# Salico_Controller_Module.net
KiCad netlist of a schematic drawn in Altium Designer
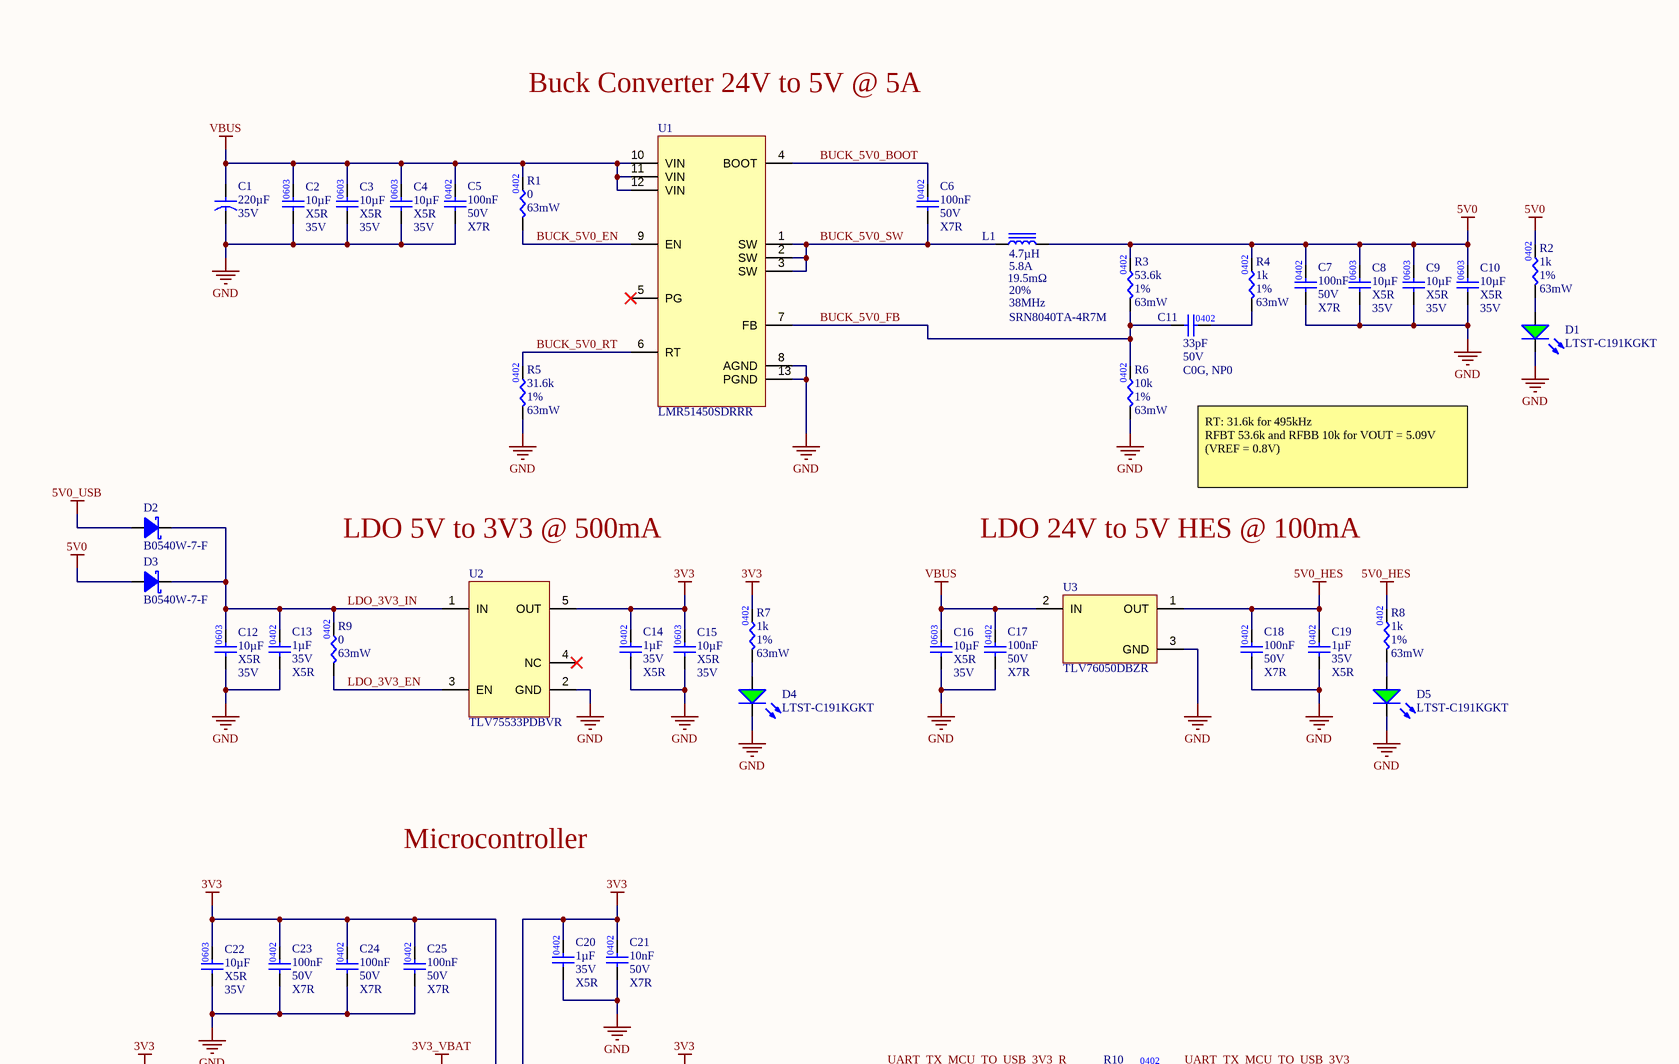
[diagram p0: Salico Controller Module.SchDoc, top left]
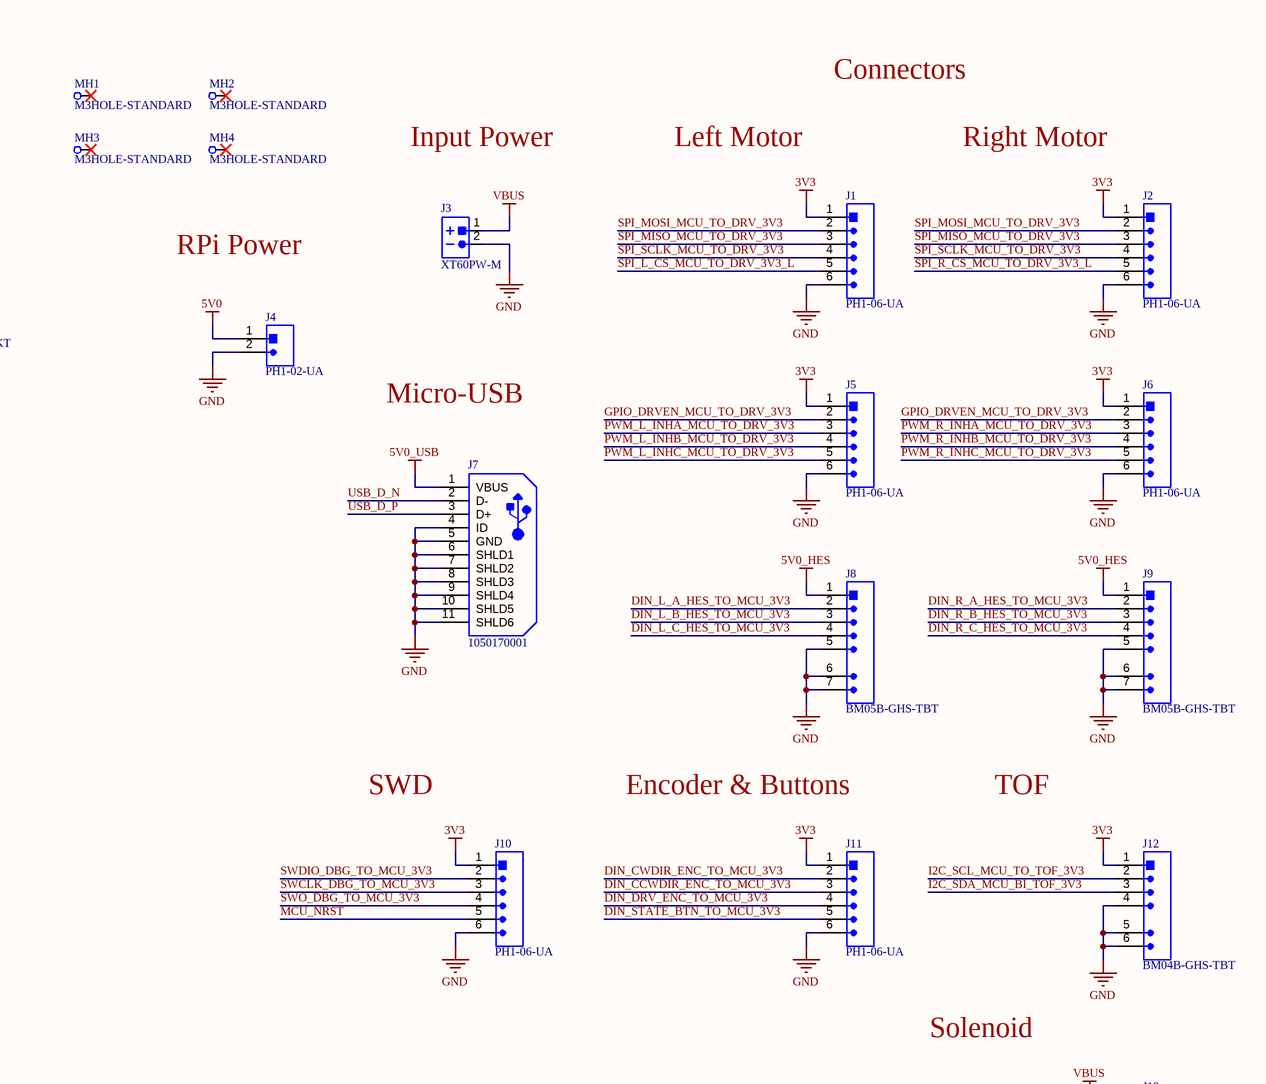
[diagram p1: Salico Controller Module.SchDoc, top right]
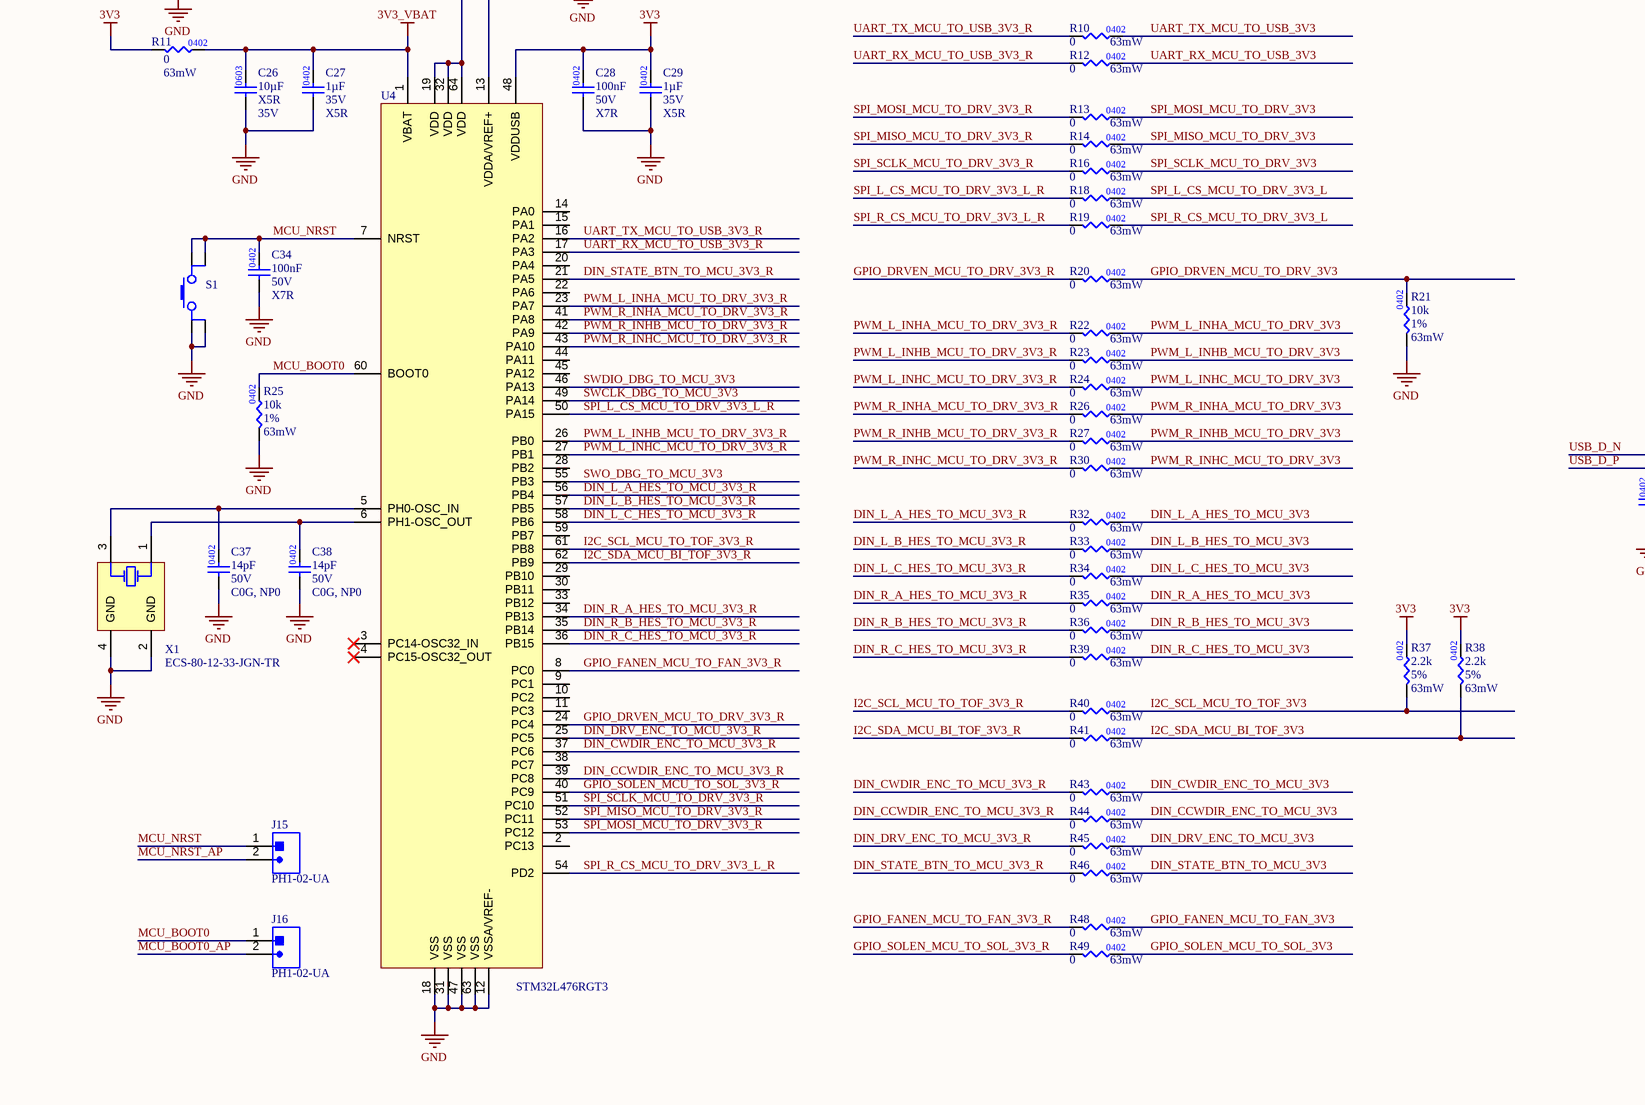
[diagram p2: Salico Controller Module.SchDoc, bottom left]
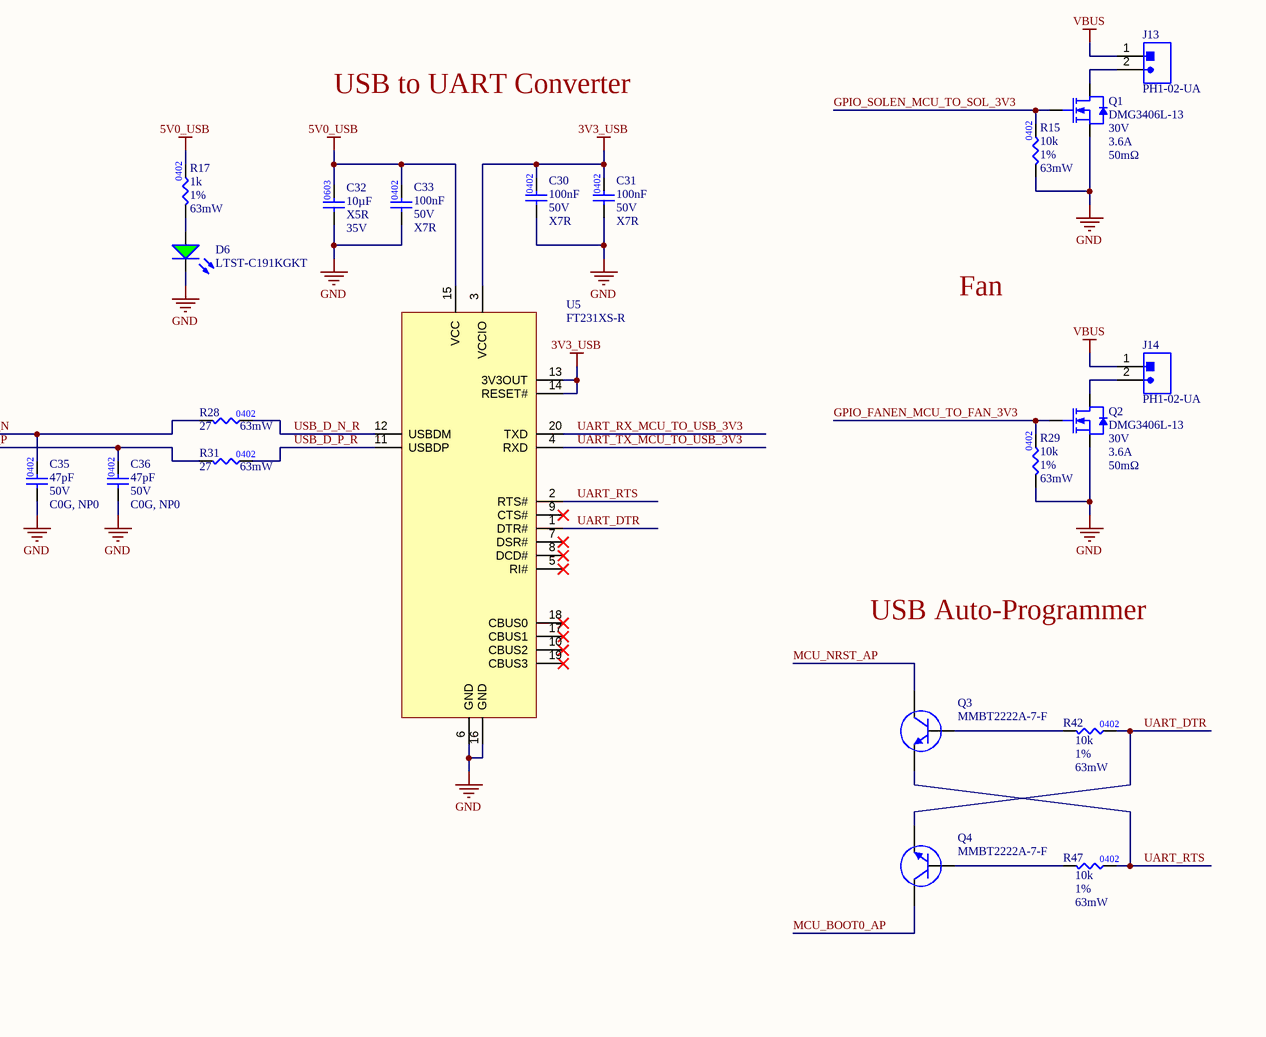
[diagram p3: Salico Controller Module.SchDoc, bottom right]

(export (version "E")
  (design (tool "Eeschema 10.0.6"))
  (components
    (comp (ref "C1")
      (value "220µF")
      (footprint "865080553014-Footprint-1")
      (description "CAP ALUM 220UF 20% 35V SMD")
      (fields
        (field (name "TOLERANCE") "20%")
        (field (name "VOLTAGE RATING") "35V")
        (field (name "Comment") "865080553014")
      )
      (libsource (lib "Americas - University of Waterloo - Kevin Li Capstone 2025") (part "865080553014-Symbol-1"))
    )
    (comp (ref "C2")
      (value "10µF")
      (footprint ".CAP_0603-Footprint-1")
      (description "CAP CER 10UF 35V X5R 0603")
      (fields
        (field (name "TEMPERATURE COEFFICIENT") "X5R")
        (field (name "VOLTAGE RATING") "35V")
        (field (name "TOLERANCE") "20%")
        (field (name "Comment") "GRM188R6YA106MA73D")
      )
      (libsource (lib "Americas - University of Waterloo - Kevin Li Capstone 2025") (part ".CAP_0603-Symbol-1"))
    )
    (comp (ref "C3")
      (value "10µF")
      (footprint ".CAP_0603-Footprint-1")
      (description "CAP CER 10UF 35V X5R 0603")
      (fields
        (field (name "TEMPERATURE COEFFICIENT") "X5R")
        (field (name "VOLTAGE RATING") "35V")
        (field (name "TOLERANCE") "20%")
        (field (name "Comment") "GRM188R6YA106MA73D")
      )
      (libsource (lib "Americas - University of Waterloo - Kevin Li Capstone 2025") (part ".CAP_0603-Symbol-1"))
    )
    (comp (ref "C4")
      (value "10µF")
      (footprint ".CAP_0603-Footprint-1")
      (description "CAP CER 10UF 35V X5R 0603")
      (fields
        (field (name "TEMPERATURE COEFFICIENT") "X5R")
        (field (name "VOLTAGE RATING") "35V")
        (field (name "TOLERANCE") "20%")
        (field (name "Comment") "GRM188R6YA106MA73D")
      )
      (libsource (lib "Americas - University of Waterloo - Kevin Li Capstone 2025") (part ".CAP_0603-Symbol-1"))
    )
    (comp (ref "C5")
      (value "100nF")
      (footprint ".CAP_0402-Footprint-1")
      (description "CAP CER 0.1UF 50V X7R 0402")
      (fields
        (field (name "VOLTAGE RATING") "50V")
        (field (name "TEMPERATURE COEFFICIENT") "X7R")
        (field (name "TOLERANCE") "10%")
        (field (name "Comment") "GCM155R71H104KE02D")
      )
      (libsource (lib "Americas - University of Waterloo - Kevin Li Capstone 2025") (part ".CAP_0402-Symbol-1"))
    )
    (comp (ref "C6")
      (value "100nF")
      (footprint ".CAP_0402-Footprint-1")
      (description "CAP CER 0.1UF 50V X7R 0402")
      (fields
        (field (name "VOLTAGE RATING") "50V")
        (field (name "TEMPERATURE COEFFICIENT") "X7R")
        (field (name "TOLERANCE") "10%")
        (field (name "Comment") "GCM155R71H104KE02D")
      )
      (libsource (lib "Americas - University of Waterloo - Kevin Li Capstone 2025") (part ".CAP_0402-Symbol-1"))
    )
    (comp (ref "C7")
      (value "100nF")
      (footprint ".CAP_0402-Footprint-1")
      (description "CAP CER 0.1UF 50V X7R 0402")
      (fields
        (field (name "VOLTAGE RATING") "50V")
        (field (name "TEMPERATURE COEFFICIENT") "X7R")
        (field (name "TOLERANCE") "10%")
        (field (name "Comment") "GCM155R71H104KE02D")
      )
      (libsource (lib "Americas - University of Waterloo - Kevin Li Capstone 2025") (part ".CAP_0402-Symbol-1"))
    )
    (comp (ref "C8")
      (value "10µF")
      (footprint ".CAP_0603-Footprint-1")
      (description "CAP CER 10UF 35V X5R 0603")
      (fields
        (field (name "TEMPERATURE COEFFICIENT") "X5R")
        (field (name "VOLTAGE RATING") "35V")
        (field (name "TOLERANCE") "20%")
        (field (name "Comment") "GRM188R6YA106MA73D")
      )
      (libsource (lib "Americas - University of Waterloo - Kevin Li Capstone 2025") (part ".CAP_0603-Symbol-1"))
    )
    (comp (ref "C9")
      (value "10µF")
      (footprint ".CAP_0603-Footprint-1")
      (description "CAP CER 10UF 35V X5R 0603")
      (fields
        (field (name "TEMPERATURE COEFFICIENT") "X5R")
        (field (name "VOLTAGE RATING") "35V")
        (field (name "TOLERANCE") "20%")
        (field (name "Comment") "GRM188R6YA106MA73D")
      )
      (libsource (lib "Americas - University of Waterloo - Kevin Li Capstone 2025") (part ".CAP_0603-Symbol-1"))
    )
    (comp (ref "C10")
      (value "10µF")
      (footprint ".CAP_0603-Footprint-1")
      (description "CAP CER 10UF 35V X5R 0603")
      (fields
        (field (name "TEMPERATURE COEFFICIENT") "X5R")
        (field (name "VOLTAGE RATING") "35V")
        (field (name "TOLERANCE") "20%")
        (field (name "Comment") "GRM188R6YA106MA73D")
      )
      (libsource (lib "Americas - University of Waterloo - Kevin Li Capstone 2025") (part ".CAP_0603-Symbol-1"))
    )
    (comp (ref "C11")
      (value "33pF")
      (footprint ".CAP_0402-Footprint-1")
      (description "CAP CER 33PF 50V C0G/NP0 0402")
      (fields
        (field (name "VOLTAGE RATING") "50V")
        (field (name "TEMPERATURE COEFFICIENT") "C0G, NP0")
        (field (name "TOLERANCE") "5%")
        (field (name "Comment") "GRM1555C1H330JA01D")
      )
      (libsource (lib "Americas - University of Waterloo - Kevin Li Capstone 2025") (part ".CAP_0402-Symbol-1"))
    )
    (comp (ref "C12")
      (value "10µF")
      (footprint ".CAP_0603-Footprint-1")
      (description "CAP CER 10UF 35V X5R 0603")
      (fields
        (field (name "TEMPERATURE COEFFICIENT") "X5R")
        (field (name "VOLTAGE RATING") "35V")
        (field (name "TOLERANCE") "20%")
        (field (name "Comment") "GRM188R6YA106MA73D")
      )
      (libsource (lib "Americas - University of Waterloo - Kevin Li Capstone 2025") (part ".CAP_0603-Symbol-1"))
    )
    (comp (ref "C13")
      (value "1µF")
      (footprint ".CAP_0402-Footprint-1")
      (description "CAP CER 1UF 35V X5R 0402")
      (fields
        (field (name "VOLTAGE RATING") "35V")
        (field (name "TEMPERATURE COEFFICIENT") "X5R")
        (field (name "TOLERANCE") "10%")
        (field (name "Comment") "GRM155R6YA105KE11D")
      )
      (libsource (lib "Americas - University of Waterloo - Kevin Li Capstone 2025") (part ".CAP_0402-Symbol-1"))
    )
    (comp (ref "C14")
      (value "1µF")
      (footprint ".CAP_0402-Footprint-1")
      (description "CAP CER 1UF 35V X5R 0402")
      (fields
        (field (name "VOLTAGE RATING") "35V")
        (field (name "TEMPERATURE COEFFICIENT") "X5R")
        (field (name "TOLERANCE") "10%")
        (field (name "Comment") "GRM155R6YA105KE11D")
      )
      (libsource (lib "Americas - University of Waterloo - Kevin Li Capstone 2025") (part ".CAP_0402-Symbol-1"))
    )
    (comp (ref "C15")
      (value "10µF")
      (footprint ".CAP_0603-Footprint-1")
      (description "CAP CER 10UF 35V X5R 0603")
      (fields
        (field (name "TEMPERATURE COEFFICIENT") "X5R")
        (field (name "VOLTAGE RATING") "35V")
        (field (name "TOLERANCE") "20%")
        (field (name "Comment") "GRM188R6YA106MA73D")
      )
      (libsource (lib "Americas - University of Waterloo - Kevin Li Capstone 2025") (part ".CAP_0603-Symbol-1"))
    )
    (comp (ref "C16")
      (value "10µF")
      (footprint ".CAP_0603-Footprint-1")
      (description "CAP CER 10UF 35V X5R 0603")
      (fields
        (field (name "TEMPERATURE COEFFICIENT") "X5R")
        (field (name "VOLTAGE RATING") "35V")
        (field (name "TOLERANCE") "20%")
        (field (name "Comment") "GRM188R6YA106MA73D")
      )
      (libsource (lib "Americas - University of Waterloo - Kevin Li Capstone 2025") (part ".CAP_0603-Symbol-1"))
    )
    (comp (ref "C17")
      (value "100nF")
      (footprint ".CAP_0402-Footprint-1")
      (description "CAP CER 0.1UF 50V X7R 0402")
      (fields
        (field (name "VOLTAGE RATING") "50V")
        (field (name "TEMPERATURE COEFFICIENT") "X7R")
        (field (name "TOLERANCE") "10%")
        (field (name "Comment") "GCM155R71H104KE02D")
      )
      (libsource (lib "Americas - University of Waterloo - Kevin Li Capstone 2025") (part ".CAP_0402-Symbol-1"))
    )
    (comp (ref "C18")
      (value "100nF")
      (footprint ".CAP_0402-Footprint-1")
      (description "CAP CER 0.1UF 50V X7R 0402")
      (fields
        (field (name "VOLTAGE RATING") "50V")
        (field (name "TEMPERATURE COEFFICIENT") "X7R")
        (field (name "TOLERANCE") "10%")
        (field (name "Comment") "GCM155R71H104KE02D")
      )
      (libsource (lib "Americas - University of Waterloo - Kevin Li Capstone 2025") (part ".CAP_0402-Symbol-1"))
    )
    (comp (ref "C19")
      (value "1µF")
      (footprint ".CAP_0402-Footprint-1")
      (description "CAP CER 1UF 35V X5R 0402")
      (fields
        (field (name "VOLTAGE RATING") "35V")
        (field (name "TEMPERATURE COEFFICIENT") "X5R")
        (field (name "TOLERANCE") "10%")
        (field (name "Comment") "GRM155R6YA105KE11D")
      )
      (libsource (lib "Americas - University of Waterloo - Kevin Li Capstone 2025") (part ".CAP_0402-Symbol-1"))
    )
    (comp (ref "C20")
      (value "1µF")
      (footprint ".CAP_0402-Footprint-1")
      (description "CAP CER 1UF 35V X5R 0402")
      (fields
        (field (name "VOLTAGE RATING") "35V")
        (field (name "TEMPERATURE COEFFICIENT") "X5R")
        (field (name "TOLERANCE") "10%")
        (field (name "Comment") "GRM155R6YA105KE11D")
      )
      (libsource (lib "Americas - University of Waterloo - Kevin Li Capstone 2025") (part ".CAP_0402-Symbol-1"))
    )
    (comp (ref "C21")
      (value "10nF")
      (footprint ".CAP_0402-Footprint-1")
      (description "CAP CER 10000PF 50V X7R 0402")
      (fields
        (field (name "VOLTAGE RATING") "50V")
        (field (name "TEMPERATURE COEFFICIENT") "X7R")
        (field (name "TOLERANCE") "10%")
        (field (name "Comment") "GCM155R71H103KA55D")
      )
      (libsource (lib "Americas - University of Waterloo - Kevin Li Capstone 2025") (part ".CAP_0402-Symbol-1"))
    )
    (comp (ref "C22")
      (value "10µF")
      (footprint ".CAP_0603-Footprint-1")
      (description "CAP CER 10UF 35V X5R 0603")
      (fields
        (field (name "TEMPERATURE COEFFICIENT") "X5R")
        (field (name "VOLTAGE RATING") "35V")
        (field (name "TOLERANCE") "20%")
        (field (name "Comment") "GRM188R6YA106MA73D")
      )
      (libsource (lib "Americas - University of Waterloo - Kevin Li Capstone 2025") (part ".CAP_0603-Symbol-1"))
    )
    (comp (ref "C23")
      (value "100nF")
      (footprint ".CAP_0402-Footprint-1")
      (description "CAP CER 0.1UF 50V X7R 0402")
      (fields
        (field (name "VOLTAGE RATING") "50V")
        (field (name "TEMPERATURE COEFFICIENT") "X7R")
        (field (name "TOLERANCE") "10%")
        (field (name "Comment") "GCM155R71H104KE02D")
      )
      (libsource (lib "Americas - University of Waterloo - Kevin Li Capstone 2025") (part ".CAP_0402-Symbol-1"))
    )
    (comp (ref "C24")
      (value "100nF")
      (footprint ".CAP_0402-Footprint-1")
      (description "CAP CER 0.1UF 50V X7R 0402")
      (fields
        (field (name "VOLTAGE RATING") "50V")
        (field (name "TEMPERATURE COEFFICIENT") "X7R")
        (field (name "TOLERANCE") "10%")
        (field (name "Comment") "GCM155R71H104KE02D")
      )
      (libsource (lib "Americas - University of Waterloo - Kevin Li Capstone 2025") (part ".CAP_0402-Symbol-1"))
    )
    (comp (ref "C25")
      (value "100nF")
      (footprint ".CAP_0402-Footprint-1")
      (description "CAP CER 0.1UF 50V X7R 0402")
      (fields
        (field (name "VOLTAGE RATING") "50V")
        (field (name "TEMPERATURE COEFFICIENT") "X7R")
        (field (name "TOLERANCE") "10%")
        (field (name "Comment") "GCM155R71H104KE02D")
      )
      (libsource (lib "Americas - University of Waterloo - Kevin Li Capstone 2025") (part ".CAP_0402-Symbol-1"))
    )
    (comp (ref "C26")
      (value "10µF")
      (footprint ".CAP_0603-Footprint-1")
      (description "CAP CER 10UF 35V X5R 0603")
      (fields
        (field (name "TEMPERATURE COEFFICIENT") "X5R")
        (field (name "VOLTAGE RATING") "35V")
        (field (name "TOLERANCE") "20%")
        (field (name "Comment") "GRM188R6YA106MA73D")
      )
      (libsource (lib "Americas - University of Waterloo - Kevin Li Capstone 2025") (part ".CAP_0603-Symbol-1"))
    )
    (comp (ref "C27")
      (value "1µF")
      (footprint ".CAP_0402-Footprint-1")
      (description "CAP CER 1UF 35V X5R 0402")
      (fields
        (field (name "VOLTAGE RATING") "35V")
        (field (name "TEMPERATURE COEFFICIENT") "X5R")
        (field (name "TOLERANCE") "10%")
        (field (name "Comment") "GRM155R6YA105KE11D")
      )
      (libsource (lib "Americas - University of Waterloo - Kevin Li Capstone 2025") (part ".CAP_0402-Symbol-1"))
    )
    (comp (ref "C28")
      (value "100nF")
      (footprint ".CAP_0402-Footprint-1")
      (description "CAP CER 0.1UF 50V X7R 0402")
      (fields
        (field (name "VOLTAGE RATING") "50V")
        (field (name "TEMPERATURE COEFFICIENT") "X7R")
        (field (name "TOLERANCE") "10%")
        (field (name "Comment") "GCM155R71H104KE02D")
      )
      (libsource (lib "Americas - University of Waterloo - Kevin Li Capstone 2025") (part ".CAP_0402-Symbol-1"))
    )
    (comp (ref "C29")
      (value "1µF")
      (footprint ".CAP_0402-Footprint-1")
      (description "CAP CER 1UF 35V X5R 0402")
      (fields
        (field (name "VOLTAGE RATING") "35V")
        (field (name "TEMPERATURE COEFFICIENT") "X5R")
        (field (name "TOLERANCE") "10%")
        (field (name "Comment") "GRM155R6YA105KE11D")
      )
      (libsource (lib "Americas - University of Waterloo - Kevin Li Capstone 2025") (part ".CAP_0402-Symbol-1"))
    )
    (comp (ref "C30")
      (value "100nF")
      (footprint ".CAP_0402-Footprint-1")
      (description "CAP CER 0.1UF 50V X7R 0402")
      (fields
        (field (name "VOLTAGE RATING") "50V")
        (field (name "TEMPERATURE COEFFICIENT") "X7R")
        (field (name "TOLERANCE") "10%")
        (field (name "Comment") "GCM155R71H104KE02D")
      )
      (libsource (lib "Americas - University of Waterloo - Kevin Li Capstone 2025") (part ".CAP_0402-Symbol-1"))
    )
    (comp (ref "C31")
      (value "100nF")
      (footprint ".CAP_0402-Footprint-1")
      (description "CAP CER 0.1UF 50V X7R 0402")
      (fields
        (field (name "VOLTAGE RATING") "50V")
        (field (name "TEMPERATURE COEFFICIENT") "X7R")
        (field (name "TOLERANCE") "10%")
        (field (name "Comment") "GCM155R71H104KE02D")
      )
      (libsource (lib "Americas - University of Waterloo - Kevin Li Capstone 2025") (part ".CAP_0402-Symbol-1"))
    )
    (comp (ref "C32")
      (value "10µF")
      (footprint ".CAP_0603-Footprint-1")
      (description "CAP CER 10UF 35V X5R 0603")
      (fields
        (field (name "TEMPERATURE COEFFICIENT") "X5R")
        (field (name "VOLTAGE RATING") "35V")
        (field (name "TOLERANCE") "20%")
        (field (name "Comment") "GRM188R6YA106MA73D")
      )
      (libsource (lib "Americas - University of Waterloo - Kevin Li Capstone 2025") (part ".CAP_0603-Symbol-1"))
    )
    (comp (ref "C33")
      (value "100nF")
      (footprint ".CAP_0402-Footprint-1")
      (description "CAP CER 0.1UF 50V X7R 0402")
      (fields
        (field (name "VOLTAGE RATING") "50V")
        (field (name "TEMPERATURE COEFFICIENT") "X7R")
        (field (name "TOLERANCE") "10%")
        (field (name "Comment") "GCM155R71H104KE02D")
      )
      (libsource (lib "Americas - University of Waterloo - Kevin Li Capstone 2025") (part ".CAP_0402-Symbol-1"))
    )
    (comp (ref "C34")
      (value "100nF")
      (footprint ".CAP_0402-Footprint-1")
      (description "CAP CER 0.1UF 50V X7R 0402")
      (fields
        (field (name "VOLTAGE RATING") "50V")
        (field (name "TEMPERATURE COEFFICIENT") "X7R")
        (field (name "TOLERANCE") "10%")
        (field (name "Comment") "GCM155R71H104KE02D")
      )
      (libsource (lib "Americas - University of Waterloo - Kevin Li Capstone 2025") (part ".CAP_0402-Symbol-1"))
    )
    (comp (ref "C35")
      (value "47pF")
      (footprint ".CAP_0402-Footprint-1")
      (description "CAP CER 47PF 50V C0G/NP0 0402")
      (fields
        (field (name "VOLTAGE RATING") "50V")
        (field (name "TEMPERATURE COEFFICIENT") "C0G, NP0")
        (field (name "TOLERANCE") "5%")
        (field (name "Comment") "GRM1555C1H470JA01D")
      )
      (libsource (lib "Americas - University of Waterloo - Kevin Li Capstone 2025") (part ".CAP_0402-Symbol-1"))
    )
    (comp (ref "C36")
      (value "47pF")
      (footprint ".CAP_0402-Footprint-1")
      (description "CAP CER 47PF 50V C0G/NP0 0402")
      (fields
        (field (name "VOLTAGE RATING") "50V")
        (field (name "TEMPERATURE COEFFICIENT") "C0G, NP0")
        (field (name "TOLERANCE") "5%")
        (field (name "Comment") "GRM1555C1H470JA01D")
      )
      (libsource (lib "Americas - University of Waterloo - Kevin Li Capstone 2025") (part ".CAP_0402-Symbol-1"))
    )
    (comp (ref "C37")
      (value "14pF")
      (footprint ".CAP_0402-Footprint-1")
      (description "CAP CER 14PF 50V C0G/NP0 0402")
      (fields
        (field (name "VOLTAGE RATING") "50V")
        (field (name "TEMPERATURE COEFFICIENT") "C0G, NP0")
        (field (name "TOLERANCE") "2%")
        (field (name "Comment") "GJM1555C1H140GB01D")
      )
      (libsource (lib "Americas - University of Waterloo - Kevin Li Capstone 2025") (part ".CAP_0402-Symbol-1"))
    )
    (comp (ref "C38")
      (value "14pF")
      (footprint ".CAP_0402-Footprint-1")
      (description "CAP CER 14PF 50V C0G/NP0 0402")
      (fields
        (field (name "VOLTAGE RATING") "50V")
        (field (name "TEMPERATURE COEFFICIENT") "C0G, NP0")
        (field (name "TOLERANCE") "2%")
        (field (name "Comment") "GJM1555C1H140GB01D")
      )
      (libsource (lib "Americas - University of Waterloo - Kevin Li Capstone 2025") (part ".CAP_0402-Symbol-1"))
    )
    (comp (ref "D1")
      (value "LTST-C191KGKT")
      (footprint "LTST-C191KGKT-Footprint-1")
      (description "LED GREEN CLEAR SMD")
      (libsource (lib "Americas - University of Waterloo - Kevin Li Capstone 2025") (part "LTST-C191KGKT-symbol"))
    )
    (comp (ref "D2")
      (value "B0540W-7-F")
      (footprint "B0540W-7-F-Footprint-1")
      (description "DIODE SCHOTTKY 40V 500MA SOD123")
      (libsource (lib "Americas - University of Waterloo - Kevin Li Capstone 2025") (part "B0540W-7-F-Symbol-1"))
    )
    (comp (ref "D3")
      (value "B0540W-7-F")
      (footprint "B0540W-7-F-Footprint-1")
      (description "DIODE SCHOTTKY 40V 500MA SOD123")
      (libsource (lib "Americas - University of Waterloo - Kevin Li Capstone 2025") (part "B0540W-7-F-Symbol-1"))
    )
    (comp (ref "D4")
      (value "LTST-C191KGKT")
      (footprint "LTST-C191KGKT-Footprint-1")
      (description "LED GREEN CLEAR SMD")
      (libsource (lib "Americas - University of Waterloo - Kevin Li Capstone 2025") (part "LTST-C191KGKT-symbol"))
    )
    (comp (ref "D5")
      (value "LTST-C191KGKT")
      (footprint "LTST-C191KGKT-Footprint-1")
      (description "LED GREEN CLEAR SMD")
      (libsource (lib "Americas - University of Waterloo - Kevin Li Capstone 2025") (part "LTST-C191KGKT-symbol"))
    )
    (comp (ref "D6")
      (value "LTST-C191KGKT")
      (footprint "LTST-C191KGKT-Footprint-1")
      (description "LED GREEN CLEAR SMD")
      (libsource (lib "Americas - University of Waterloo - Kevin Li Capstone 2025") (part "LTST-C191KGKT-symbol"))
    )
    (comp (ref "J1")
      (value "PH1-06-UA")
      (footprint "PH1-06-UA-Footprint-1")
      (description "CONN HEADER VERT 6POS 2.54MM")
      (libsource (lib "Americas - University of Waterloo - Kevin Li Capstone 2025") (part "PH1-06-UA-Symbol-1"))
    )
    (comp (ref "J2")
      (value "PH1-06-UA")
      (footprint "PH1-06-UA-Footprint-1")
      (description "CONN HEADER VERT 6POS 2.54MM")
      (libsource (lib "Americas - University of Waterloo - Kevin Li Capstone 2025") (part "PH1-06-UA-Symbol-1"))
    )
    (comp (ref "J3")
      (value "XT60PW-M")
      (footprint "XT60PW-M-Footprint-1")
      (description "XT60PW-M Connector")
      (libsource (lib "Americas - University of Waterloo - Kevin Li Capstone 2025") (part "XT60PW-M-Symbol-1"))
    )
    (comp (ref "J4")
      (value "PH1-02-UA")
      (footprint "PH1-02-UA-Footprint-1")
      (description "CONN HEADER VERT 2POS 2.54MM")
      (libsource (lib "Americas - University of Waterloo - Kevin Li Capstone 2025") (part "PH1-02-UA-Symbol-1"))
    )
    (comp (ref "J5")
      (value "PH1-06-UA")
      (footprint "PH1-06-UA-Footprint-1")
      (description "CONN HEADER VERT 6POS 2.54MM")
      (libsource (lib "Americas - University of Waterloo - Kevin Li Capstone 2025") (part "PH1-06-UA-Symbol-1"))
    )
    (comp (ref "J6")
      (value "PH1-06-UA")
      (footprint "PH1-06-UA-Footprint-1")
      (description "CONN HEADER VERT 6POS 2.54MM")
      (libsource (lib "Americas - University of Waterloo - Kevin Li Capstone 2025") (part "PH1-06-UA-Symbol-1"))
    )
    (comp (ref "J7")
      (value "1050170001")
      (footprint "1050170001-Footprint-1")
      (description "CONN RCPT USB2.0 MICRO B SMD R/A")
      (libsource (lib "Americas - University of Waterloo - Kevin Li Capstone 2025") (part "1050170001-Symbol-1"))
    )
    (comp (ref "J8")
      (value "BM05B-GHS-TBT")
      (footprint "BM05B-GHS-TBT-Footprint-1")
      (description "CONN HEADER SMD 5POS 1.25MM")
      (libsource (lib "Americas - University of Waterloo - Kevin Li Capstone 2025") (part "BM05B-GHS-TBT-Symbol-1"))
    )
    (comp (ref "J9")
      (value "BM05B-GHS-TBT")
      (footprint "BM05B-GHS-TBT-Footprint-1")
      (description "CONN HEADER SMD 5POS 1.25MM")
      (libsource (lib "Americas - University of Waterloo - Kevin Li Capstone 2025") (part "BM05B-GHS-TBT-Symbol-1"))
    )
    (comp (ref "J10")
      (value "PH1-06-UA")
      (footprint "PH1-06-UA-Footprint-1")
      (description "CONN HEADER VERT 6POS 2.54MM")
      (libsource (lib "Americas - University of Waterloo - Kevin Li Capstone 2025") (part "PH1-06-UA-Symbol-1"))
    )
    (comp (ref "J11")
      (value "PH1-06-UA")
      (footprint "PH1-06-UA-Footprint-1")
      (description "CONN HEADER VERT 6POS 2.54MM")
      (libsource (lib "Americas - University of Waterloo - Kevin Li Capstone 2025") (part "PH1-06-UA-Symbol-1"))
    )
    (comp (ref "J12")
      (value "BM04B-GHS-TBT")
      (footprint "BM04B-GHS-TBT-Footprint-1")
      (description "CONN HEADER SMD 4POS 1.25MM")
      (libsource (lib "Americas - University of Waterloo - Kevin Li Capstone 2025") (part "BM04B-GHS-TBT-Symbol-1"))
    )
    (comp (ref "J13")
      (value "PH1-02-UA")
      (footprint "PH1-02-UA-Footprint-1")
      (description "CONN HEADER VERT 2POS 2.54MM")
      (libsource (lib "Americas - University of Waterloo - Kevin Li Capstone 2025") (part "PH1-02-UA-Symbol-1"))
    )
    (comp (ref "J14")
      (value "PH1-02-UA")
      (footprint "PH1-02-UA-Footprint-1")
      (description "CONN HEADER VERT 2POS 2.54MM")
      (libsource (lib "Americas - University of Waterloo - Kevin Li Capstone 2025") (part "PH1-02-UA-Symbol-1"))
    )
    (comp (ref "J15")
      (value "PH1-02-UA")
      (footprint "PH1-02-UA-Footprint-1")
      (description "CONN HEADER VERT 2POS 2.54MM")
      (libsource (lib "Americas - University of Waterloo - Kevin Li Capstone 2025") (part "PH1-02-UA-Symbol-1"))
    )
    (comp (ref "J16")
      (value "PH1-02-UA")
      (footprint "PH1-02-UA-Footprint-1")
      (description "CONN HEADER VERT 2POS 2.54MM")
      (libsource (lib "Americas - University of Waterloo - Kevin Li Capstone 2025") (part "PH1-02-UA-Symbol-1"))
    )
    (comp (ref "L1")
      (value "SRN8040TA-4R7M")
      (footprint "SRN8040TA-4R7M-Footprint-1")
      (description "FIXED IND 4.7UH 5.8A 19.5MOHM SM")
      (fields
        (field (name "ALTIUM_VALUE") "4.7µH")
        (field (name "CURRENT RATING") "5.8A")
        (field (name "DC RESISTANCE") "19.5mΩ")
        (field (name "TOLERANCE") "20%")
        (field (name "SELF RESONANT FREQUENCY") "38MHz")
      )
      (libsource (lib "Americas - University of Waterloo - Kevin Li Capstone 2025") (part "SRN8040TA-4R7M"))
    )
    (comp (ref "MH1")
      (value "M3HOLE-STANDARD")
      (footprint "M3HOLE-STANDARD-Footprint-1")
      (description "M3 Mounting Hole")
      (libsource (lib "Americas - University of Waterloo - Kevin Li Capstone 2025") (part "M3HOLE-STANDARD-Symbol-1"))
    )
    (comp (ref "MH2")
      (value "M3HOLE-STANDARD")
      (footprint "M3HOLE-STANDARD-Footprint-1")
      (description "M3 Mounting Hole")
      (libsource (lib "Americas - University of Waterloo - Kevin Li Capstone 2025") (part "M3HOLE-STANDARD-Symbol-1"))
    )
    (comp (ref "MH3")
      (value "M3HOLE-STANDARD")
      (footprint "M3HOLE-STANDARD-Footprint-1")
      (description "M3 Mounting Hole")
      (libsource (lib "Americas - University of Waterloo - Kevin Li Capstone 2025") (part "M3HOLE-STANDARD-Symbol-1"))
    )
    (comp (ref "MH4")
      (value "M3HOLE-STANDARD")
      (footprint "M3HOLE-STANDARD-Footprint-1")
      (description "M3 Mounting Hole")
      (libsource (lib "Americas - University of Waterloo - Kevin Li Capstone 2025") (part "M3HOLE-STANDARD-Symbol-1"))
    )
    (comp (ref "Q1")
      (value "DMG3406L-13")
      (footprint "DMG3406L-13-Footprint-1")
      (description "MOSFET N-CH 30V 3.6A SOT23")
      (fields
        (field (name "DRAIN TO SOURCE VOLTAGE") "30V")
        (field (name "CONTINUOUS DRAIN CURRENT") "3.6A")
        (field (name "RDSON") "50mΩ")
      )
      (libsource (lib "Americas - University of Waterloo - Kevin Li Capstone 2025") (part "DMG3406L-13-symbol-1"))
    )
    (comp (ref "Q2")
      (value "DMG3406L-13")
      (footprint "DMG3406L-13-Footprint-1")
      (description "MOSFET N-CH 30V 3.6A SOT23")
      (fields
        (field (name "DRAIN TO SOURCE VOLTAGE") "30V")
        (field (name "CONTINUOUS DRAIN CURRENT") "3.6A")
        (field (name "RDSON") "50mΩ")
      )
      (libsource (lib "Americas - University of Waterloo - Kevin Li Capstone 2025") (part "DMG3406L-13-symbol-1"))
    )
    (comp (ref "Q3")
      (value "MMBT2222A-7-F")
      (footprint "MMBT2222A-7-F-Footprint-1")
      (description "TRANS NPN 40V 0.6A SOT-23-3")
      (libsource (lib "Americas - University of Waterloo - Kevin Li Capstone 2025") (part "MMBT2222A-7-F-Symbol-1"))
    )
    (comp (ref "Q4")
      (value "MMBT2222A-7-F")
      (footprint "MMBT2222A-7-F-Footprint-1")
      (description "TRANS NPN 40V 0.6A SOT-23-3")
      (libsource (lib "Americas - University of Waterloo - Kevin Li Capstone 2025") (part "MMBT2222A-7-F-Symbol-1"))
    )
    (comp (ref "R1")
      (value "0")
      (footprint ".RES_0402-Footprint-1")
      (description "RES 0 OHM JUMPER 1/16W 0402")
      (fields (field (name "POWER") "63mW") (field (name "Comment") "RC0402JR-070RL"))
      (libsource (lib "Americas - University of Waterloo - Kevin Li Capstone 2025") (part ".RES_0402-Symbol-1"))
    )
    (comp (ref "R2")
      (value "1k")
      (footprint ".RES_0402-Footprint-1")
      (description "RES 1K OHM 1% 1/16W 0402")
      (fields
        (field (name "TOLERANCE") "1%")
        (field (name "POWER") "63mW")
        (field (name "Comment") "RC0402FR-071KL")
      )
      (libsource (lib "Americas - University of Waterloo - Kevin Li Capstone 2025") (part ".RES_0402-Symbol-1"))
    )
    (comp (ref "R3")
      (value "53.6k")
      (footprint ".RES_0402-Footprint-1")
      (description "RES 53.6K OHM 1% 1/16W 0402")
      (fields
        (field (name "TOLERANCE") "1%")
        (field (name "POWER") "63mW")
        (field (name "Comment") "RC0402FR-0753K6L")
      )
      (libsource (lib "Americas - University of Waterloo - Kevin Li Capstone 2025") (part ".RES_0402-Symbol-1"))
    )
    (comp (ref "R4")
      (value "1k")
      (footprint ".RES_0402-Footprint-1")
      (description "RES 1K OHM 1% 1/16W 0402")
      (fields
        (field (name "TOLERANCE") "1%")
        (field (name "POWER") "63mW")
        (field (name "Comment") "RC0402FR-071KL")
      )
      (libsource (lib "Americas - University of Waterloo - Kevin Li Capstone 2025") (part ".RES_0402-Symbol-1"))
    )
    (comp (ref "R5")
      (value "31.6k")
      (footprint ".RES_0402-Footprint-1")
      (description "RES 31.6K OHM 1% 1/16W 0402")
      (fields
        (field (name "TOLERANCE") "1%")
        (field (name "POWER") "63mW")
        (field (name "Comment") "RC0402FR-0731K6L")
      )
      (libsource (lib "Americas - University of Waterloo - Kevin Li Capstone 2025") (part ".RES_0402-Symbol-1"))
    )
    (comp (ref "R6")
      (value "10k")
      (footprint ".RES_0402-Footprint-1")
      (description "RES 10K OHM 1% 1/16W 0402")
      (fields
        (field (name "TOLERANCE") "1%")
        (field (name "POWER") "63mW")
        (field (name "Comment") "RC0402FR-0710KL")
      )
      (libsource (lib "Americas - University of Waterloo - Kevin Li Capstone 2025") (part ".RES_0402-Symbol-1"))
    )
    (comp (ref "R7")
      (value "1k")
      (footprint ".RES_0402-Footprint-1")
      (description "RES 1K OHM 1% 1/16W 0402")
      (fields
        (field (name "TOLERANCE") "1%")
        (field (name "POWER") "63mW")
        (field (name "Comment") "RC0402FR-071KL")
      )
      (libsource (lib "Americas - University of Waterloo - Kevin Li Capstone 2025") (part ".RES_0402-Symbol-1"))
    )
    (comp (ref "R8")
      (value "1k")
      (footprint ".RES_0402-Footprint-1")
      (description "RES 1K OHM 1% 1/16W 0402")
      (fields
        (field (name "TOLERANCE") "1%")
        (field (name "POWER") "63mW")
        (field (name "Comment") "RC0402FR-071KL")
      )
      (libsource (lib "Americas - University of Waterloo - Kevin Li Capstone 2025") (part ".RES_0402-Symbol-1"))
    )
    (comp (ref "R9")
      (value "0")
      (footprint ".RES_0402-Footprint-1")
      (description "RES 0 OHM JUMPER 1/16W 0402")
      (fields (field (name "POWER") "63mW") (field (name "Comment") "RC0402JR-070RL"))
      (libsource (lib "Americas - University of Waterloo - Kevin Li Capstone 2025") (part ".RES_0402-Symbol-1"))
    )
    (comp (ref "R10")
      (value "0")
      (footprint ".RES_0402-Footprint-1")
      (description "RES 0 OHM JUMPER 1/16W 0402")
      (fields (field (name "POWER") "63mW") (field (name "Comment") "RC0402JR-070RL"))
      (libsource (lib "Americas - University of Waterloo - Kevin Li Capstone 2025") (part ".RES_0402-Symbol-1"))
    )
    (comp (ref "R11")
      (value "0")
      (footprint ".RES_0402-Footprint-1")
      (description "RES 0 OHM JUMPER 1/16W 0402")
      (fields (field (name "POWER") "63mW") (field (name "Comment") "RC0402JR-070RL"))
      (libsource (lib "Americas - University of Waterloo - Kevin Li Capstone 2025") (part ".RES_0402-Symbol-1"))
    )
    (comp (ref "R12")
      (value "0")
      (footprint ".RES_0402-Footprint-1")
      (description "RES 0 OHM JUMPER 1/16W 0402")
      (fields (field (name "POWER") "63mW") (field (name "Comment") "RC0402JR-070RL"))
      (libsource (lib "Americas - University of Waterloo - Kevin Li Capstone 2025") (part ".RES_0402-Symbol-1"))
    )
    (comp (ref "R13")
      (value "0")
      (footprint ".RES_0402-Footprint-1")
      (description "RES 0 OHM JUMPER 1/16W 0402")
      (fields (field (name "POWER") "63mW") (field (name "Comment") "RC0402JR-070RL"))
      (libsource (lib "Americas - University of Waterloo - Kevin Li Capstone 2025") (part ".RES_0402-Symbol-1"))
    )
    (comp (ref "R14")
      (value "0")
      (footprint ".RES_0402-Footprint-1")
      (description "RES 0 OHM JUMPER 1/16W 0402")
      (fields (field (name "POWER") "63mW") (field (name "Comment") "RC0402JR-070RL"))
      (libsource (lib "Americas - University of Waterloo - Kevin Li Capstone 2025") (part ".RES_0402-Symbol-1"))
    )
    (comp (ref "R15")
      (value "10k")
      (footprint ".RES_0402-Footprint-1")
      (description "RES 10K OHM 1% 1/16W 0402")
      (fields
        (field (name "TOLERANCE") "1%")
        (field (name "POWER") "63mW")
        (field (name "Comment") "RC0402FR-0710KL")
      )
      (libsource (lib "Americas - University of Waterloo - Kevin Li Capstone 2025") (part ".RES_0402-Symbol-1"))
    )
    (comp (ref "R16")
      (value "0")
      (footprint ".RES_0402-Footprint-1")
      (description "RES 0 OHM JUMPER 1/16W 0402")
      (fields (field (name "POWER") "63mW") (field (name "Comment") "RC0402JR-070RL"))
      (libsource (lib "Americas - University of Waterloo - Kevin Li Capstone 2025") (part ".RES_0402-Symbol-1"))
    )
    (comp (ref "R17")
      (value "1k")
      (footprint ".RES_0402-Footprint-1")
      (description "RES 1K OHM 1% 1/16W 0402")
      (fields
        (field (name "TOLERANCE") "1%")
        (field (name "POWER") "63mW")
        (field (name "Comment") "RC0402FR-071KL")
      )
      (libsource (lib "Americas - University of Waterloo - Kevin Li Capstone 2025") (part ".RES_0402-Symbol-1"))
    )
    (comp (ref "R18")
      (value "0")
      (footprint ".RES_0402-Footprint-1")
      (description "RES 0 OHM JUMPER 1/16W 0402")
      (fields (field (name "POWER") "63mW") (field (name "Comment") "RC0402JR-070RL"))
      (libsource (lib "Americas - University of Waterloo - Kevin Li Capstone 2025") (part ".RES_0402-Symbol-1"))
    )
    (comp (ref "R19")
      (value "0")
      (footprint ".RES_0402-Footprint-1")
      (description "RES 0 OHM JUMPER 1/16W 0402")
      (fields (field (name "POWER") "63mW") (field (name "Comment") "RC0402JR-070RL"))
      (libsource (lib "Americas - University of Waterloo - Kevin Li Capstone 2025") (part ".RES_0402-Symbol-1"))
    )
    (comp (ref "R20")
      (value "0")
      (footprint ".RES_0402-Footprint-1")
      (description "RES 0 OHM JUMPER 1/16W 0402")
      (fields (field (name "POWER") "63mW") (field (name "Comment") "RC0402JR-070RL"))
      (libsource (lib "Americas - University of Waterloo - Kevin Li Capstone 2025") (part ".RES_0402-Symbol-1"))
    )
    (comp (ref "R21")
      (value "10k")
      (footprint ".RES_0402-Footprint-1")
      (description "RES 10K OHM 1% 1/16W 0402")
      (fields
        (field (name "TOLERANCE") "1%")
        (field (name "POWER") "63mW")
        (field (name "Comment") "RC0402FR-0710KL")
      )
      (libsource (lib "Americas - University of Waterloo - Kevin Li Capstone 2025") (part ".RES_0402-Symbol-1"))
    )
    (comp (ref "R22")
      (value "0")
      (footprint ".RES_0402-Footprint-1")
      (description "RES 0 OHM JUMPER 1/16W 0402")
      (fields (field (name "POWER") "63mW") (field (name "Comment") "RC0402JR-070RL"))
      (libsource (lib "Americas - University of Waterloo - Kevin Li Capstone 2025") (part ".RES_0402-Symbol-1"))
    )
    (comp (ref "R23")
      (value "0")
      (footprint ".RES_0402-Footprint-1")
      (description "RES 0 OHM JUMPER 1/16W 0402")
      (fields (field (name "POWER") "63mW") (field (name "Comment") "RC0402JR-070RL"))
      (libsource (lib "Americas - University of Waterloo - Kevin Li Capstone 2025") (part ".RES_0402-Symbol-1"))
    )
    (comp (ref "R24")
      (value "0")
      (footprint ".RES_0402-Footprint-1")
      (description "RES 0 OHM JUMPER 1/16W 0402")
      (fields (field (name "POWER") "63mW") (field (name "Comment") "RC0402JR-070RL"))
      (libsource (lib "Americas - University of Waterloo - Kevin Li Capstone 2025") (part ".RES_0402-Symbol-1"))
    )
    (comp (ref "R25")
      (value "10k")
      (footprint ".RES_0402-Footprint-1")
      (description "RES 10K OHM 1% 1/16W 0402")
      (fields
        (field (name "TOLERANCE") "1%")
        (field (name "POWER") "63mW")
        (field (name "Comment") "RC0402FR-0710KL")
      )
      (libsource (lib "Americas - University of Waterloo - Kevin Li Capstone 2025") (part ".RES_0402-Symbol-1"))
    )
    (comp (ref "R26")
      (value "0")
      (footprint ".RES_0402-Footprint-1")
      (description "RES 0 OHM JUMPER 1/16W 0402")
      (fields (field (name "POWER") "63mW") (field (name "Comment") "RC0402JR-070RL"))
      (libsource (lib "Americas - University of Waterloo - Kevin Li Capstone 2025") (part ".RES_0402-Symbol-1"))
    )
    (comp (ref "R27")
      (value "0")
      (footprint ".RES_0402-Footprint-1")
      (description "RES 0 OHM JUMPER 1/16W 0402")
      (fields (field (name "POWER") "63mW") (field (name "Comment") "RC0402JR-070RL"))
      (libsource (lib "Americas - University of Waterloo - Kevin Li Capstone 2025") (part ".RES_0402-Symbol-1"))
    )
    (comp (ref "R28")
      (value "27")
      (footprint ".RES_0402-Footprint-1")
      (description "RES 27 OHM 1% 1/16W 0402")
      (fields
        (field (name "TOLERANCE") "1%")
        (field (name "POWER") "63mW")
        (field (name "Comment") "RC0402FR-0727RL")
      )
      (libsource (lib "Americas - University of Waterloo - Kevin Li Capstone 2025") (part ".RES_0402-Symbol-1"))
    )
    (comp (ref "R29")
      (value "10k")
      (footprint ".RES_0402-Footprint-1")
      (description "RES 10K OHM 1% 1/16W 0402")
      (fields
        (field (name "TOLERANCE") "1%")
        (field (name "POWER") "63mW")
        (field (name "Comment") "RC0402FR-0710KL")
      )
      (libsource (lib "Americas - University of Waterloo - Kevin Li Capstone 2025") (part ".RES_0402-Symbol-1"))
    )
    (comp (ref "R30")
      (value "0")
      (footprint ".RES_0402-Footprint-1")
      (description "RES 0 OHM JUMPER 1/16W 0402")
      (fields (field (name "POWER") "63mW") (field (name "Comment") "RC0402JR-070RL"))
      (libsource (lib "Americas - University of Waterloo - Kevin Li Capstone 2025") (part ".RES_0402-Symbol-1"))
    )
    (comp (ref "R31")
      (value "27")
      (footprint ".RES_0402-Footprint-1")
      (description "RES 27 OHM 1% 1/16W 0402")
      (fields
        (field (name "TOLERANCE") "1%")
        (field (name "POWER") "63mW")
        (field (name "Comment") "RC0402FR-0727RL")
      )
      (libsource (lib "Americas - University of Waterloo - Kevin Li Capstone 2025") (part ".RES_0402-Symbol-1"))
    )
    (comp (ref "R32")
      (value "0")
      (footprint ".RES_0402-Footprint-1")
      (description "RES 0 OHM JUMPER 1/16W 0402")
      (fields (field (name "POWER") "63mW") (field (name "Comment") "RC0402JR-070RL"))
      (libsource (lib "Americas - University of Waterloo - Kevin Li Capstone 2025") (part ".RES_0402-Symbol-1"))
    )
    (comp (ref "R33")
      (value "0")
      (footprint ".RES_0402-Footprint-1")
      (description "RES 0 OHM JUMPER 1/16W 0402")
      (fields (field (name "POWER") "63mW") (field (name "Comment") "RC0402JR-070RL"))
      (libsource (lib "Americas - University of Waterloo - Kevin Li Capstone 2025") (part ".RES_0402-Symbol-1"))
    )
    (comp (ref "R34")
      (value "0")
      (footprint ".RES_0402-Footprint-1")
      (description "RES 0 OHM JUMPER 1/16W 0402")
      (fields (field (name "POWER") "63mW") (field (name "Comment") "RC0402JR-070RL"))
      (libsource (lib "Americas - University of Waterloo - Kevin Li Capstone 2025") (part ".RES_0402-Symbol-1"))
    )
    (comp (ref "R35")
      (value "0")
      (footprint ".RES_0402-Footprint-1")
      (description "RES 0 OHM JUMPER 1/16W 0402")
      (fields (field (name "POWER") "63mW") (field (name "Comment") "RC0402JR-070RL"))
      (libsource (lib "Americas - University of Waterloo - Kevin Li Capstone 2025") (part ".RES_0402-Symbol-1"))
    )
    (comp (ref "R36")
      (value "0")
      (footprint ".RES_0402-Footprint-1")
      (description "RES 0 OHM JUMPER 1/16W 0402")
      (fields (field (name "POWER") "63mW") (field (name "Comment") "RC0402JR-070RL"))
      (libsource (lib "Americas - University of Waterloo - Kevin Li Capstone 2025") (part ".RES_0402-Symbol-1"))
    )
    (comp (ref "R37")
      (value "2.2k")
      (footprint ".RES_0402-Footprint-1")
      (description "RES 2.2K OHM 5% 1/16W 0402")
      (fields
        (field (name "TOLERANCE") "5%")
        (field (name "POWER") "63mW")
        (field (name "Comment") "RC0402JR-072K2L")
      )
      (libsource (lib "Americas - University of Waterloo - Kevin Li Capstone 2025") (part ".RES_0402-Symbol-1"))
    )
    (comp (ref "R38")
      (value "2.2k")
      (footprint ".RES_0402-Footprint-1")
      (description "RES 2.2K OHM 5% 1/16W 0402")
      (fields
        (field (name "TOLERANCE") "5%")
        (field (name "POWER") "63mW")
        (field (name "Comment") "RC0402JR-072K2L")
      )
      (libsource (lib "Americas - University of Waterloo - Kevin Li Capstone 2025") (part ".RES_0402-Symbol-1"))
    )
    (comp (ref "R39")
      (value "0")
      (footprint ".RES_0402-Footprint-1")
      (description "RES 0 OHM JUMPER 1/16W 0402")
      (fields (field (name "POWER") "63mW") (field (name "Comment") "RC0402JR-070RL"))
      (libsource (lib "Americas - University of Waterloo - Kevin Li Capstone 2025") (part ".RES_0402-Symbol-1"))
    )
    (comp (ref "R40")
      (value "0")
      (footprint ".RES_0402-Footprint-1")
      (description "RES 0 OHM JUMPER 1/16W 0402")
      (fields (field (name "POWER") "63mW") (field (name "Comment") "RC0402JR-070RL"))
      (libsource (lib "Americas - University of Waterloo - Kevin Li Capstone 2025") (part ".RES_0402-Symbol-1"))
    )
    (comp (ref "R41")
      (value "0")
      (footprint ".RES_0402-Footprint-1")
      (description "RES 0 OHM JUMPER 1/16W 0402")
      (fields (field (name "POWER") "63mW") (field (name "Comment") "RC0402JR-070RL"))
      (libsource (lib "Americas - University of Waterloo - Kevin Li Capstone 2025") (part ".RES_0402-Symbol-1"))
    )
    (comp (ref "R42")
      (value "10k")
      (footprint ".RES_0402-Footprint-1")
      (description "RES 10K OHM 1% 1/16W 0402")
      (fields
        (field (name "TOLERANCE") "1%")
        (field (name "POWER") "63mW")
        (field (name "Comment") "RC0402FR-0710KL")
      )
      (libsource (lib "Americas - University of Waterloo - Kevin Li Capstone 2025") (part ".RES_0402-Symbol-1"))
    )
    (comp (ref "R43")
      (value "0")
      (footprint ".RES_0402-Footprint-1")
      (description "RES 0 OHM JUMPER 1/16W 0402")
      (fields (field (name "POWER") "63mW") (field (name "Comment") "RC0402JR-070RL"))
      (libsource (lib "Americas - University of Waterloo - Kevin Li Capstone 2025") (part ".RES_0402-Symbol-1"))
    )
    (comp (ref "R44")
      (value "0")
      (footprint ".RES_0402-Footprint-1")
      (description "RES 0 OHM JUMPER 1/16W 0402")
      (fields (field (name "POWER") "63mW") (field (name "Comment") "RC0402JR-070RL"))
      (libsource (lib "Americas - University of Waterloo - Kevin Li Capstone 2025") (part ".RES_0402-Symbol-1"))
    )
    (comp (ref "R45")
      (value "0")
      (footprint ".RES_0402-Footprint-1")
      (description "RES 0 OHM JUMPER 1/16W 0402")
      (fields (field (name "POWER") "63mW") (field (name "Comment") "RC0402JR-070RL"))
      (libsource (lib "Americas - University of Waterloo - Kevin Li Capstone 2025") (part ".RES_0402-Symbol-1"))
    )
    (comp (ref "R46")
      (value "0")
      (footprint ".RES_0402-Footprint-1")
      (description "RES 0 OHM JUMPER 1/16W 0402")
      (fields (field (name "POWER") "63mW") (field (name "Comment") "RC0402JR-070RL"))
      (libsource (lib "Americas - University of Waterloo - Kevin Li Capstone 2025") (part ".RES_0402-Symbol-1"))
    )
    (comp (ref "R47")
      (value "10k")
      (footprint ".RES_0402-Footprint-1")
      (description "RES 10K OHM 1% 1/16W 0402")
      (fields
        (field (name "TOLERANCE") "1%")
        (field (name "POWER") "63mW")
        (field (name "Comment") "RC0402FR-0710KL")
      )
      (libsource (lib "Americas - University of Waterloo - Kevin Li Capstone 2025") (part ".RES_0402-Symbol-1"))
    )
    (comp (ref "R48")
      (value "0")
      (footprint ".RES_0402-Footprint-1")
      (description "RES 0 OHM JUMPER 1/16W 0402")
      (fields (field (name "POWER") "63mW") (field (name "Comment") "RC0402JR-070RL"))
      (libsource (lib "Americas - University of Waterloo - Kevin Li Capstone 2025") (part ".RES_0402-Symbol-1"))
    )
    (comp (ref "R49")
      (value "0")
      (footprint ".RES_0402-Footprint-1")
      (description "RES 0 OHM JUMPER 1/16W 0402")
      (fields (field (name "POWER") "63mW") (field (name "Comment") "RC0402JR-070RL"))
      (libsource (lib "Americas - University of Waterloo - Kevin Li Capstone 2025") (part ".RES_0402-Symbol-1"))
    )
    (comp (ref "S1")
      (value "PTS647SN38SMTR2 LFS")
      (footprint "PTS647SN38SMTR2 LFS-Footprint-1")
      (description "SWITCH TACTILE SPST-NO 0.05A 12V")
      (libsource (lib "Americas - University of Waterloo - Kevin Li Capstone 2025") (part "PTS647SN38SMTR2 LFS-Symbol-1"))
    )
    (comp (ref "U1")
      (value "LMR51450SDRRR")
      (footprint "SON50P300X80_HS-13N")
      (description "IC REG BUCK ADJ 5A 12WSON")
      (libsource (lib "Americas - University of Waterloo - Kevin Li Capstone 2025") (part "LMR51450SDRRR"))
    )
    (comp (ref "U2")
      (value "TLV75533PDBVR")
      (footprint "TLV75533PDBVR-Footprint-1")
      (description "IC REG LINEAR 3.3V 500MA SOT23-5")
      (libsource (lib "Americas - University of Waterloo - Kevin Li Capstone 2025") (part "TLV75533PDBVR-Symbol-1"))
    )
    (comp (ref "U3")
      (value "TLV76050DBZR")
      (footprint "TLV76050DBZR-Footprint-1")
      (description "IC REG LINEAR 5V 100MA SOT23-3")
      (libsource (lib "Americas - University of Waterloo - Kevin Li Capstone 2025") (part "TLV76050DBZR-Symbol-1"))
    )
    (comp (ref "U4")
      (value "STM32L476RGT3")
      (footprint "STM32L476RGT3-Footprint-1")
      (description "IC MCU 32BIT 1MB FLASH 64LQFP")
      (libsource (lib "Americas - University of Waterloo - Kevin Li Capstone 2025") (part "STM32L476RGT3-Symbol-1"))
    )
    (comp (ref "U5")
      (value "FT231XS-R")
      (footprint "SOP64P600X175-20N")
      (description "IC USB SERIAL FULL UART 20SSOP")
      (libsource (lib "Americas - University of Waterloo - Kevin Li Capstone 2025") (part "FT231XS-R-Symbol-1"))
    )
    (comp (ref "X1")
      (value "ECS-80-12-33-JGN-TR")
      (footprint "ECS-80-12-33-JGN-TR-Footprint-1")
      (description "CRYSTAL 8.0000MHZ 12PF SMD")
      (libsource (lib "Americas - University of Waterloo - Kevin Li Capstone 2025") (part "ECS-80-12-33-JGN-TR-Symbol-1"))
    )
  )
  (nets
    (net (code "1") (name "/BUCK_5V0_BOOT") (class "Default")
      (node (ref "C6") (pin "2") (pinfunction "2_2") (pintype "passive"))
      (node (ref "U1") (pin "4") (pinfunction "BOOT_4") (pintype "passive"))
    )
    (net (code "2") (name "/BUCK_5V0_EN") (class "Default")
      (node (ref "R1") (pin "1") (pinfunction "1_1") (pintype "passive"))
      (node (ref "U1") (pin "9") (pinfunction "EN_9") (pintype "passive"))
    )
    (net (code "3") (name "/BUCK_5V0_FB") (class "Default")
      (node (ref "C11") (pin "1") (pinfunction "1_1") (pintype "passive"))
      (node (ref "R3") (pin "1") (pinfunction "1_1") (pintype "passive"))
      (node (ref "R6") (pin "2") (pinfunction "2_2") (pintype "passive"))
      (node (ref "U1") (pin "7") (pinfunction "FB_7") (pintype "passive"))
    )
    (net (code "4") (name "/BUCK_5V0_RT") (class "Default")
      (node (ref "R5") (pin "2") (pinfunction "2_2") (pintype "passive"))
      (node (ref "U1") (pin "6") (pinfunction "RT_6") (pintype "passive"))
    )
    (net (code "5") (name "/BUCK_5V0_SW") (class "Default")
      (node (ref "C6") (pin "1") (pinfunction "1_1") (pintype "passive"))
      (node (ref "L1") (pin "1") (pinfunction "1_1") (pintype "passive"))
      (node (ref "U1") (pin "1") (pinfunction "SW_1") (pintype "passive"))
      (node (ref "U1") (pin "2") (pinfunction "SW_2") (pintype "passive"))
      (node (ref "U1") (pin "3") (pinfunction "SW_3") (pintype "passive"))
    )
    (net (code "6") (name "/DIN_CCWDIR_ENC_TO_MCU_3V3") (class "Default")
      (node (ref "J11") (pin "3") (pinfunction "3_3") (pintype "passive"))
      (node (ref "R44") (pin "2") (pinfunction "2_2") (pintype "passive"))
    )
    (net (code "7") (name "/DIN_CCWDIR_ENC_TO_MCU_3V3_R") (class "Default")
      (node (ref "R44") (pin "1") (pinfunction "1_1") (pintype "passive"))
      (node (ref "U4") (pin "39") (pinfunction "PC8_39") (pintype "passive"))
    )
    (net (code "8") (name "/DIN_CWDIR_ENC_TO_MCU_3V3") (class "Default")
      (node (ref "J11") (pin "2") (pinfunction "2_2") (pintype "passive"))
      (node (ref "R43") (pin "2") (pinfunction "2_2") (pintype "passive"))
    )
    (net (code "9") (name "/DIN_CWDIR_ENC_TO_MCU_3V3_R") (class "Default")
      (node (ref "R43") (pin "1") (pinfunction "1_1") (pintype "passive"))
      (node (ref "U4") (pin "37") (pinfunction "PC6_37") (pintype "passive"))
    )
    (net (code "10") (name "/DIN_DRV_ENC_TO_MCU_3V3") (class "Default")
      (node (ref "J11") (pin "4") (pinfunction "4_4") (pintype "passive"))
      (node (ref "R45") (pin "2") (pinfunction "2_2") (pintype "passive"))
    )
    (net (code "11") (name "/DIN_DRV_ENC_TO_MCU_3V3_R") (class "Default")
      (node (ref "R45") (pin "1") (pinfunction "1_1") (pintype "passive"))
      (node (ref "U4") (pin "25") (pinfunction "PC5_25") (pintype "passive"))
    )
    (net (code "12") (name "/DIN_L_A_HES_TO_MCU_3V3") (class "Default")
      (node (ref "J8") (pin "2") (pinfunction "2_2") (pintype "passive"))
      (node (ref "R32") (pin "2") (pinfunction "2_2") (pintype "passive"))
    )
    (net (code "13") (name "/DIN_L_A_HES_TO_MCU_3V3_R") (class "Default")
      (node (ref "R32") (pin "1") (pinfunction "1_1") (pintype "passive"))
      (node (ref "U4") (pin "56") (pinfunction "PB4_56") (pintype "passive"))
    )
    (net (code "14") (name "/DIN_L_B_HES_TO_MCU_3V3") (class "Default")
      (node (ref "J8") (pin "3") (pinfunction "3_3") (pintype "passive"))
      (node (ref "R33") (pin "2") (pinfunction "2_2") (pintype "passive"))
    )
    (net (code "15") (name "/DIN_L_B_HES_TO_MCU_3V3_R") (class "Default")
      (node (ref "R33") (pin "1") (pinfunction "1_1") (pintype "passive"))
      (node (ref "U4") (pin "57") (pinfunction "PB5_57") (pintype "passive"))
    )
    (net (code "16") (name "/DIN_L_C_HES_TO_MCU_3V3") (class "Default")
      (node (ref "J8") (pin "4") (pinfunction "4_4") (pintype "passive"))
      (node (ref "R34") (pin "2") (pinfunction "2_2") (pintype "passive"))
    )
    (net (code "17") (name "/DIN_L_C_HES_TO_MCU_3V3_R") (class "Default")
      (node (ref "R34") (pin "1") (pinfunction "1_1") (pintype "passive"))
      (node (ref "U4") (pin "58") (pinfunction "PB6_58") (pintype "passive"))
    )
    (net (code "18") (name "/DIN_R_A_HES_TO_MCU_3V3") (class "Default")
      (node (ref "J9") (pin "2") (pinfunction "2_2") (pintype "passive"))
      (node (ref "R35") (pin "2") (pinfunction "2_2") (pintype "passive"))
    )
    (net (code "19") (name "/DIN_R_A_HES_TO_MCU_3V3_R") (class "Default")
      (node (ref "R35") (pin "1") (pinfunction "1_1") (pintype "passive"))
      (node (ref "U4") (pin "34") (pinfunction "PB13_34") (pintype "passive"))
    )
    (net (code "20") (name "/DIN_R_B_HES_TO_MCU_3V3") (class "Default")
      (node (ref "J9") (pin "3") (pinfunction "3_3") (pintype "passive"))
      (node (ref "R36") (pin "2") (pinfunction "2_2") (pintype "passive"))
    )
    (net (code "21") (name "/DIN_R_B_HES_TO_MCU_3V3_R") (class "Default")
      (node (ref "R36") (pin "1") (pinfunction "1_1") (pintype "passive"))
      (node (ref "U4") (pin "35") (pinfunction "PB14_35") (pintype "passive"))
    )
    (net (code "22") (name "/DIN_R_C_HES_TO_MCU_3V3") (class "Default")
      (node (ref "J9") (pin "4") (pinfunction "4_4") (pintype "passive"))
      (node (ref "R39") (pin "2") (pinfunction "2_2") (pintype "passive"))
    )
    (net (code "23") (name "/DIN_R_C_HES_TO_MCU_3V3_R") (class "Default")
      (node (ref "R39") (pin "1") (pinfunction "1_1") (pintype "passive"))
      (node (ref "U4") (pin "36") (pinfunction "PB15_36") (pintype "passive"))
    )
    (net (code "24") (name "/DIN_STATE_BTN_TO_MCU_3V3") (class "Default")
      (node (ref "J11") (pin "5") (pinfunction "5_5") (pintype "passive"))
      (node (ref "R46") (pin "2") (pinfunction "2_2") (pintype "passive"))
    )
    (net (code "25") (name "/DIN_STATE_BTN_TO_MCU_3V3_R") (class "Default")
      (node (ref "R46") (pin "1") (pinfunction "1_1") (pintype "passive"))
      (node (ref "U4") (pin "21") (pinfunction "PA5_21") (pintype "passive"))
    )
    (net (code "26") (name "/GPIO_DRVEN_MCU_TO_DRV_3V3") (class "Default")
      (node (ref "J5") (pin "2") (pinfunction "2_2") (pintype "passive"))
      (node (ref "J6") (pin "2") (pinfunction "2_2") (pintype "passive"))
      (node (ref "R20") (pin "2") (pinfunction "2_2") (pintype "passive"))
      (node (ref "R21") (pin "2") (pinfunction "2_2") (pintype "passive"))
    )
    (net (code "27") (name "/GPIO_DRVEN_MCU_TO_DRV_3V3_R") (class "Default")
      (node (ref "R20") (pin "1") (pinfunction "1_1") (pintype "passive"))
      (node (ref "U4") (pin "24") (pinfunction "PC4_24") (pintype "passive"))
    )
    (net (code "28") (name "/GPIO_FANEN_MCU_TO_FAN_3V3") (class "Default")
      (node (ref "Q2") (pin "1") (pinfunction "G_1") (pintype "passive"))
      (node (ref "R29") (pin "2") (pinfunction "2_2") (pintype "passive"))
      (node (ref "R48") (pin "2") (pinfunction "2_2") (pintype "passive"))
    )
    (net (code "29") (name "/GPIO_FANEN_MCU_TO_FAN_3V3_R") (class "Default")
      (node (ref "R48") (pin "1") (pinfunction "1_1") (pintype "passive"))
      (node (ref "U4") (pin "8") (pinfunction "PC0_8") (pintype "passive"))
    )
    (net (code "30") (name "/GPIO_SOLEN_MCU_TO_SOL_3V3") (class "Default")
      (node (ref "Q1") (pin "1") (pinfunction "G_1") (pintype "passive"))
      (node (ref "R15") (pin "2") (pinfunction "2_2") (pintype "passive"))
      (node (ref "R49") (pin "2") (pinfunction "2_2") (pintype "passive"))
    )
    (net (code "31") (name "/GPIO_SOLEN_MCU_TO_SOL_3V3_R") (class "Default")
      (node (ref "R49") (pin "1") (pinfunction "1_1") (pintype "passive"))
      (node (ref "U4") (pin "40") (pinfunction "PC9_40") (pintype "passive"))
    )
    (net (code "32") (name "/I2C_SCL_MCU_TO_TOF_3V3") (class "Default")
      (node (ref "J12") (pin "2") (pinfunction "2_2") (pintype "passive"))
      (node (ref "R37") (pin "1") (pinfunction "1_1") (pintype "passive"))
      (node (ref "R40") (pin "2") (pinfunction "2_2") (pintype "passive"))
    )
    (net (code "33") (name "/I2C_SCL_MCU_TO_TOF_3V3_R") (class "Default")
      (node (ref "R40") (pin "1") (pinfunction "1_1") (pintype "passive"))
      (node (ref "U4") (pin "61") (pinfunction "PB8_61") (pintype "passive"))
    )
    (net (code "34") (name "/I2C_SDA_MCU_BI_TOF_3V3") (class "Default")
      (node (ref "J12") (pin "3") (pinfunction "3_3") (pintype "passive"))
      (node (ref "R38") (pin "1") (pinfunction "1_1") (pintype "passive"))
      (node (ref "R41") (pin "2") (pinfunction "2_2") (pintype "passive"))
    )
    (net (code "35") (name "/I2C_SDA_MCU_BI_TOF_3V3_R") (class "Default")
      (node (ref "R41") (pin "1") (pinfunction "1_1") (pintype "passive"))
      (node (ref "U4") (pin "62") (pinfunction "PB9_62") (pintype "passive"))
    )
    (net (code "36") (name "/LDO_3V3_EN") (class "Default")
      (node (ref "R9") (pin "1") (pinfunction "1_1") (pintype "passive"))
      (node (ref "U2") (pin "3") (pinfunction "EN_3") (pintype "passive"))
    )
    (net (code "37") (name "/LDO_3V3_IN") (class "Default")
      (node (ref "C12") (pin "2") (pinfunction "2_2") (pintype "passive"))
      (node (ref "C13") (pin "2") (pinfunction "2_2") (pintype "passive"))
      (node (ref "D2") (pin "2") (pinfunction "Cathode_2") (pintype "passive"))
      (node (ref "D3") (pin "2") (pinfunction "Cathode_2") (pintype "passive"))
      (node (ref "R9") (pin "2") (pinfunction "2_2") (pintype "passive"))
      (node (ref "U2") (pin "1") (pinfunction "IN_1") (pintype "passive"))
    )
    (net (code "38") (name "/MCU_BOOT0") (class "Default")
      (node (ref "J16") (pin "1") (pinfunction "1_1") (pintype "passive"))
      (node (ref "R25") (pin "2") (pinfunction "2_2") (pintype "passive"))
      (node (ref "U4") (pin "60") (pinfunction "BOOT0_60") (pintype "passive"))
    )
    (net (code "39") (name "/MCU_BOOT0_AP") (class "Default")
      (node (ref "J16") (pin "2") (pinfunction "2_2") (pintype "passive"))
      (node (ref "Q4") (pin "3") (pinfunction "C_3") (pintype "passive"))
    )
    (net (code "40") (name "/MCU_NRST") (class "Default")
      (node (ref "C34") (pin "2") (pinfunction "2_2") (pintype "passive"))
      (node (ref "J10") (pin "5") (pinfunction "5_5") (pintype "passive"))
      (node (ref "J15") (pin "1") (pinfunction "1_1") (pintype "passive"))
      (node (ref "S1") (pin "3") (pinfunction "3_3") (pintype "passive"))
      (node (ref "S1") (pin "4") (pinfunction "4_4") (pintype "passive"))
      (node (ref "U4") (pin "7") (pinfunction "NRST_7") (pintype "passive"))
    )
    (net (code "41") (name "/MCU_NRST_AP") (class "Default")
      (node (ref "J15") (pin "2") (pinfunction "2_2") (pintype "passive"))
      (node (ref "Q3") (pin "3") (pinfunction "C_3") (pintype "passive"))
    )
    (net (code "42") (name "/PWM_L_INHA_MCU_TO_DRV_3V3") (class "Default")
      (node (ref "J5") (pin "3") (pinfunction "3_3") (pintype "passive"))
      (node (ref "R22") (pin "2") (pinfunction "2_2") (pintype "passive"))
    )
    (net (code "43") (name "/PWM_L_INHA_MCU_TO_DRV_3V3_R") (class "Default")
      (node (ref "R22") (pin "1") (pinfunction "1_1") (pintype "passive"))
      (node (ref "U4") (pin "23") (pinfunction "PA7_23") (pintype "passive"))
    )
    (net (code "44") (name "/PWM_L_INHB_MCU_TO_DRV_3V3") (class "Default")
      (node (ref "J5") (pin "4") (pinfunction "4_4") (pintype "passive"))
      (node (ref "R23") (pin "2") (pinfunction "2_2") (pintype "passive"))
    )
    (net (code "45") (name "/PWM_L_INHB_MCU_TO_DRV_3V3_R") (class "Default")
      (node (ref "R23") (pin "1") (pinfunction "1_1") (pintype "passive"))
      (node (ref "U4") (pin "26") (pinfunction "PB0_26") (pintype "passive"))
    )
    (net (code "46") (name "/PWM_L_INHC_MCU_TO_DRV_3V3") (class "Default")
      (node (ref "J5") (pin "5") (pinfunction "5_5") (pintype "passive"))
      (node (ref "R24") (pin "2") (pinfunction "2_2") (pintype "passive"))
    )
    (net (code "47") (name "/PWM_L_INHC_MCU_TO_DRV_3V3_R") (class "Default")
      (node (ref "R24") (pin "1") (pinfunction "1_1") (pintype "passive"))
      (node (ref "U4") (pin "27") (pinfunction "PB1_27") (pintype "passive"))
    )
    (net (code "48") (name "/PWM_R_INHA_MCU_TO_DRV_3V3") (class "Default")
      (node (ref "J6") (pin "3") (pinfunction "3_3") (pintype "passive"))
      (node (ref "R26") (pin "2") (pinfunction "2_2") (pintype "passive"))
    )
    (net (code "49") (name "/PWM_R_INHA_MCU_TO_DRV_3V3_R") (class "Default")
      (node (ref "R26") (pin "1") (pinfunction "1_1") (pintype "passive"))
      (node (ref "U4") (pin "41") (pinfunction "PA8_41") (pintype "passive"))
    )
    (net (code "50") (name "/PWM_R_INHB_MCU_TO_DRV_3V3") (class "Default")
      (node (ref "J6") (pin "4") (pinfunction "4_4") (pintype "passive"))
      (node (ref "R27") (pin "2") (pinfunction "2_2") (pintype "passive"))
    )
    (net (code "51") (name "/PWM_R_INHB_MCU_TO_DRV_3V3_R") (class "Default")
      (node (ref "R27") (pin "1") (pinfunction "1_1") (pintype "passive"))
      (node (ref "U4") (pin "42") (pinfunction "PA9_42") (pintype "passive"))
    )
    (net (code "52") (name "/PWM_R_INHC_MCU_TO_DRV_3V3") (class "Default")
      (node (ref "J6") (pin "5") (pinfunction "5_5") (pintype "passive"))
      (node (ref "R30") (pin "2") (pinfunction "2_2") (pintype "passive"))
    )
    (net (code "53") (name "/PWM_R_INHC_MCU_TO_DRV_3V3_R") (class "Default")
      (node (ref "R30") (pin "1") (pinfunction "1_1") (pintype "passive"))
      (node (ref "U4") (pin "43") (pinfunction "PA10_43") (pintype "passive"))
    )
    (net (code "54") (name "/SPI_L_CS_MCU_TO_DRV_3V3_L") (class "Default")
      (node (ref "J1") (pin "5") (pinfunction "5_5") (pintype "passive"))
      (node (ref "R18") (pin "2") (pinfunction "2_2") (pintype "passive"))
    )
    (net (code "55") (name "/SPI_L_CS_MCU_TO_DRV_3V3_L_R") (class "Default")
      (node (ref "R18") (pin "1") (pinfunction "1_1") (pintype "passive"))
      (node (ref "U4") (pin "50") (pinfunction "PA15_50") (pintype "passive"))
    )
    (net (code "56") (name "/SPI_MISO_MCU_TO_DRV_3V3") (class "Default")
      (node (ref "J1") (pin "3") (pinfunction "3_3") (pintype "passive"))
      (node (ref "J2") (pin "3") (pinfunction "3_3") (pintype "passive"))
      (node (ref "R14") (pin "2") (pinfunction "2_2") (pintype "passive"))
    )
    (net (code "57") (name "/SPI_MISO_MCU_TO_DRV_3V3_R") (class "Default")
      (node (ref "R14") (pin "1") (pinfunction "1_1") (pintype "passive"))
      (node (ref "U4") (pin "52") (pinfunction "PC11_52") (pintype "passive"))
    )
    (net (code "58") (name "/SPI_MOSI_MCU_TO_DRV_3V3") (class "Default")
      (node (ref "J1") (pin "2") (pinfunction "2_2") (pintype "passive"))
      (node (ref "J2") (pin "2") (pinfunction "2_2") (pintype "passive"))
      (node (ref "R13") (pin "2") (pinfunction "2_2") (pintype "passive"))
    )
    (net (code "59") (name "/SPI_MOSI_MCU_TO_DRV_3V3_R") (class "Default")
      (node (ref "R13") (pin "1") (pinfunction "1_1") (pintype "passive"))
      (node (ref "U4") (pin "53") (pinfunction "PC12_53") (pintype "passive"))
    )
    (net (code "60") (name "/SPI_R_CS_MCU_TO_DRV_3V3_L") (class "Default")
      (node (ref "J2") (pin "5") (pinfunction "5_5") (pintype "passive"))
      (node (ref "R19") (pin "2") (pinfunction "2_2") (pintype "passive"))
    )
    (net (code "61") (name "/SPI_R_CS_MCU_TO_DRV_3V3_L_R") (class "Default")
      (node (ref "R19") (pin "1") (pinfunction "1_1") (pintype "passive"))
      (node (ref "U4") (pin "54") (pinfunction "PD2_54") (pintype "passive"))
    )
    (net (code "62") (name "/SPI_SCLK_MCU_TO_DRV_3V3") (class "Default")
      (node (ref "J1") (pin "4") (pinfunction "4_4") (pintype "passive"))
      (node (ref "J2") (pin "4") (pinfunction "4_4") (pintype "passive"))
      (node (ref "R16") (pin "2") (pinfunction "2_2") (pintype "passive"))
    )
    (net (code "63") (name "/SPI_SCLK_MCU_TO_DRV_3V3_R") (class "Default")
      (node (ref "R16") (pin "1") (pinfunction "1_1") (pintype "passive"))
      (node (ref "U4") (pin "51") (pinfunction "PC10_51") (pintype "passive"))
    )
    (net (code "64") (name "/SWCLK_DBG_TO_MCU_3V3") (class "Default")
      (node (ref "J10") (pin "3") (pinfunction "3_3") (pintype "passive"))
      (node (ref "U4") (pin "49") (pinfunction "PA14_49") (pintype "passive"))
    )
    (net (code "65") (name "/SWDIO_DBG_TO_MCU_3V3") (class "Default")
      (node (ref "J10") (pin "2") (pinfunction "2_2") (pintype "passive"))
      (node (ref "U4") (pin "46") (pinfunction "PA13_46") (pintype "passive"))
    )
    (net (code "66") (name "/SWO_DBG_TO_MCU_3V3") (class "Default")
      (node (ref "J10") (pin "4") (pinfunction "4_4") (pintype "passive"))
      (node (ref "U4") (pin "55") (pinfunction "PB3_55") (pintype "passive"))
    )
    (net (code "67") (name "/UART_DTR") (class "Default")
      (node (ref "Q4") (pin "1") (pinfunction "E_1") (pintype "passive"))
      (node (ref "R42") (pin "2") (pinfunction "2_2") (pintype "passive"))
      (node (ref "U5") (pin "1") (pinfunction "DTR#_1") (pintype "passive"))
    )
    (net (code "68") (name "/UART_RTS") (class "Default")
      (node (ref "Q3") (pin "1") (pinfunction "E_1") (pintype "passive"))
      (node (ref "R47") (pin "2") (pinfunction "2_2") (pintype "passive"))
      (node (ref "U5") (pin "2") (pinfunction "RTS#_2") (pintype "passive"))
    )
    (net (code "69") (name "/UART_RX_MCU_TO_USB_3V3") (class "Default")
      (node (ref "R12") (pin "2") (pinfunction "2_2") (pintype "passive"))
      (node (ref "U5") (pin "20") (pinfunction "TXD_20") (pintype "passive"))
    )
    (net (code "70") (name "/UART_RX_MCU_TO_USB_3V3_R") (class "Default")
      (node (ref "R12") (pin "1") (pinfunction "1_1") (pintype "passive"))
      (node (ref "U4") (pin "17") (pinfunction "PA3_17") (pintype "passive"))
    )
    (net (code "71") (name "/UART_TX_MCU_TO_USB_3V3") (class "Default")
      (node (ref "R10") (pin "2") (pinfunction "2_2") (pintype "passive"))
      (node (ref "U5") (pin "4") (pinfunction "RXD_4") (pintype "passive"))
    )
    (net (code "72") (name "/UART_TX_MCU_TO_USB_3V3_R") (class "Default")
      (node (ref "R10") (pin "1") (pinfunction "1_1") (pintype "passive"))
      (node (ref "U4") (pin "16") (pinfunction "PA2_16") (pintype "passive"))
    )
    (net (code "73") (name "/USB_D_N") (class "Default")
      (node (ref "C35") (pin "2") (pinfunction "2_2") (pintype "passive"))
      (node (ref "J7") (pin "2") (pinfunction "D-_2") (pintype "passive"))
      (node (ref "R28") (pin "1") (pinfunction "1_1") (pintype "passive"))
    )
    (net (code "74") (name "/USB_D_N_R") (class "Default")
      (node (ref "R28") (pin "2") (pinfunction "2_2") (pintype "passive"))
      (node (ref "U5") (pin "12") (pinfunction "USBDM_12") (pintype "passive"))
    )
    (net (code "75") (name "/USB_D_P") (class "Default")
      (node (ref "C36") (pin "2") (pinfunction "2_2") (pintype "passive"))
      (node (ref "J7") (pin "3") (pinfunction "D+_3") (pintype "passive"))
      (node (ref "R31") (pin "1") (pinfunction "1_1") (pintype "passive"))
    )
    (net (code "76") (name "/USB_D_P_R") (class "Default")
      (node (ref "R31") (pin "2") (pinfunction "2_2") (pintype "passive"))
      (node (ref "U5") (pin "11") (pinfunction "USBDP_11") (pintype "passive"))
    )
    (net (code "77") (name "3V3") (class "Default")
      (node (ref "C14") (pin "2") (pinfunction "2_2") (pintype "passive"))
      (node (ref "C15") (pin "2") (pinfunction "2_2") (pintype "passive"))
      (node (ref "C20") (pin "2") (pinfunction "2_2") (pintype "passive"))
      (node (ref "C21") (pin "2") (pinfunction "2_2") (pintype "passive"))
      (node (ref "C22") (pin "2") (pinfunction "2_2") (pintype "passive"))
      (node (ref "C23") (pin "2") (pinfunction "2_2") (pintype "passive"))
      (node (ref "C24") (pin "2") (pinfunction "2_2") (pintype "passive"))
      (node (ref "C25") (pin "2") (pinfunction "2_2") (pintype "passive"))
      (node (ref "C28") (pin "2") (pinfunction "2_2") (pintype "passive"))
      (node (ref "C29") (pin "2") (pinfunction "2_2") (pintype "passive"))
      (node (ref "J1") (pin "1") (pinfunction "1_1") (pintype "passive"))
      (node (ref "J10") (pin "1") (pinfunction "1_1") (pintype "passive"))
      (node (ref "J11") (pin "1") (pinfunction "1_1") (pintype "passive"))
      (node (ref "J12") (pin "1") (pinfunction "1_1") (pintype "passive"))
      (node (ref "J2") (pin "1") (pinfunction "1_1") (pintype "passive"))
      (node (ref "J5") (pin "1") (pinfunction "1_1") (pintype "passive"))
      (node (ref "J6") (pin "1") (pinfunction "1_1") (pintype "passive"))
      (node (ref "R11") (pin "1") (pinfunction "1_1") (pintype "passive"))
      (node (ref "R37") (pin "2") (pinfunction "2_2") (pintype "passive"))
      (node (ref "R38") (pin "2") (pinfunction "2_2") (pintype "passive"))
      (node (ref "R7") (pin "2") (pinfunction "2_2") (pintype "passive"))
      (node (ref "U2") (pin "5") (pinfunction "OUT_5") (pintype "passive"))
      (node (ref "U4") (pin "13") (pinfunction "VDDA/VREF+_13") (pintype "passive"))
      (node (ref "U4") (pin "19") (pinfunction "VDD_19") (pintype "passive"))
      (node (ref "U4") (pin "32") (pinfunction "VDD_32") (pintype "passive"))
      (node (ref "U4") (pin "48") (pinfunction "VDDUSB_48") (pintype "passive"))
      (node (ref "U4") (pin "64") (pinfunction "VDD_64") (pintype "passive"))
    )
    (net (code "78") (name "3V3_USB") (class "Default")
      (node (ref "C30") (pin "2") (pinfunction "2_2") (pintype "passive"))
      (node (ref "C31") (pin "2") (pinfunction "2_2") (pintype "passive"))
      (node (ref "U5") (pin "13") (pinfunction "3V3OUT_13") (pintype "passive"))
      (node (ref "U5") (pin "14") (pinfunction "RESET#_14") (pintype "passive"))
      (node (ref "U5") (pin "3") (pinfunction "VCCIO_3") (pintype "passive"))
    )
    (net (code "79") (name "3V3_VBAT") (class "Default")
      (node (ref "C26") (pin "2") (pinfunction "2_2") (pintype "passive"))
      (node (ref "C27") (pin "2") (pinfunction "2_2") (pintype "passive"))
      (node (ref "R11") (pin "2") (pinfunction "2_2") (pintype "passive"))
      (node (ref "U4") (pin "1") (pinfunction "VBAT_1") (pintype "passive"))
    )
    (net (code "80") (name "5V0") (class "Default")
      (node (ref "C10") (pin "2") (pinfunction "2_2") (pintype "passive"))
      (node (ref "C7") (pin "2") (pinfunction "2_2") (pintype "passive"))
      (node (ref "C8") (pin "2") (pinfunction "2_2") (pintype "passive"))
      (node (ref "C9") (pin "2") (pinfunction "2_2") (pintype "passive"))
      (node (ref "D3") (pin "1") (pinfunction "Anode_1") (pintype "passive"))
      (node (ref "J4") (pin "1") (pinfunction "1_1") (pintype "passive"))
      (node (ref "L1") (pin "2") (pinfunction "2_2") (pintype "passive"))
      (node (ref "R2") (pin "2") (pinfunction "2_2") (pintype "passive"))
      (node (ref "R3") (pin "2") (pinfunction "2_2") (pintype "passive"))
      (node (ref "R4") (pin "2") (pinfunction "2_2") (pintype "passive"))
    )
    (net (code "81") (name "5V0_HES") (class "Default")
      (node (ref "C18") (pin "2") (pinfunction "2_2") (pintype "passive"))
      (node (ref "C19") (pin "2") (pinfunction "2_2") (pintype "passive"))
      (node (ref "J8") (pin "1") (pinfunction "1_1") (pintype "passive"))
      (node (ref "J9") (pin "1") (pinfunction "1_1") (pintype "passive"))
      (node (ref "R8") (pin "2") (pinfunction "2_2") (pintype "passive"))
      (node (ref "U3") (pin "1") (pinfunction "OUT_1") (pintype "passive"))
    )
    (net (code "82") (name "5V0_USB") (class "Default")
      (node (ref "C32") (pin "2") (pinfunction "2_2") (pintype "passive"))
      (node (ref "C33") (pin "2") (pinfunction "2_2") (pintype "passive"))
      (node (ref "D2") (pin "1") (pinfunction "Anode_1") (pintype "passive"))
      (node (ref "J7") (pin "1") (pinfunction "VBUS_1") (pintype "passive"))
      (node (ref "R17") (pin "2") (pinfunction "2_2") (pintype "passive"))
      (node (ref "U5") (pin "15") (pinfunction "VCC_15") (pintype "passive"))
    )
    (net (code "83") (name "GND") (class "Default")
      (node (ref "C1") (pin "2") (pinfunction "2_2") (pintype "passive"))
      (node (ref "C10") (pin "1") (pinfunction "1_1") (pintype "passive"))
      (node (ref "C12") (pin "1") (pinfunction "1_1") (pintype "passive"))
      (node (ref "C13") (pin "1") (pinfunction "1_1") (pintype "passive"))
      (node (ref "C14") (pin "1") (pinfunction "1_1") (pintype "passive"))
      (node (ref "C15") (pin "1") (pinfunction "1_1") (pintype "passive"))
      (node (ref "C16") (pin "1") (pinfunction "1_1") (pintype "passive"))
      (node (ref "C17") (pin "1") (pinfunction "1_1") (pintype "passive"))
      (node (ref "C18") (pin "1") (pinfunction "1_1") (pintype "passive"))
      (node (ref "C19") (pin "1") (pinfunction "1_1") (pintype "passive"))
      (node (ref "C2") (pin "1") (pinfunction "1_1") (pintype "passive"))
      (node (ref "C20") (pin "1") (pinfunction "1_1") (pintype "passive"))
      (node (ref "C21") (pin "1") (pinfunction "1_1") (pintype "passive"))
      (node (ref "C22") (pin "1") (pinfunction "1_1") (pintype "passive"))
      (node (ref "C23") (pin "1") (pinfunction "1_1") (pintype "passive"))
      (node (ref "C24") (pin "1") (pinfunction "1_1") (pintype "passive"))
      (node (ref "C25") (pin "1") (pinfunction "1_1") (pintype "passive"))
      (node (ref "C26") (pin "1") (pinfunction "1_1") (pintype "passive"))
      (node (ref "C27") (pin "1") (pinfunction "1_1") (pintype "passive"))
      (node (ref "C28") (pin "1") (pinfunction "1_1") (pintype "passive"))
      (node (ref "C29") (pin "1") (pinfunction "1_1") (pintype "passive"))
      (node (ref "C3") (pin "1") (pinfunction "1_1") (pintype "passive"))
      (node (ref "C30") (pin "1") (pinfunction "1_1") (pintype "passive"))
      (node (ref "C31") (pin "1") (pinfunction "1_1") (pintype "passive"))
      (node (ref "C32") (pin "1") (pinfunction "1_1") (pintype "passive"))
      (node (ref "C33") (pin "1") (pinfunction "1_1") (pintype "passive"))
      (node (ref "C34") (pin "1") (pinfunction "1_1") (pintype "passive"))
      (node (ref "C35") (pin "1") (pinfunction "1_1") (pintype "passive"))
      (node (ref "C36") (pin "1") (pinfunction "1_1") (pintype "passive"))
      (node (ref "C37") (pin "1") (pinfunction "1_1") (pintype "passive"))
      (node (ref "C38") (pin "1") (pinfunction "1_1") (pintype "passive"))
      (node (ref "C4") (pin "1") (pinfunction "1_1") (pintype "passive"))
      (node (ref "C5") (pin "1") (pinfunction "1_1") (pintype "passive"))
      (node (ref "C7") (pin "1") (pinfunction "1_1") (pintype "passive"))
      (node (ref "C8") (pin "1") (pinfunction "1_1") (pintype "passive"))
      (node (ref "C9") (pin "1") (pinfunction "1_1") (pintype "passive"))
      (node (ref "D1") (pin "2") (pinfunction "K_2") (pintype "passive"))
      (node (ref "D4") (pin "2") (pinfunction "K_2") (pintype "passive"))
      (node (ref "D5") (pin "2") (pinfunction "K_2") (pintype "passive"))
      (node (ref "D6") (pin "2") (pinfunction "K_2") (pintype "passive"))
      (node (ref "J1") (pin "6") (pinfunction "6_6") (pintype "passive"))
      (node (ref "J10") (pin "6") (pinfunction "6_6") (pintype "passive"))
      (node (ref "J11") (pin "6") (pinfunction "6_6") (pintype "passive"))
      (node (ref "J12") (pin "4") (pinfunction "4_4") (pintype "passive"))
      (node (ref "J12") (pin "5") (pinfunction "5_5") (pintype "passive"))
      (node (ref "J12") (pin "6") (pinfunction "6_6") (pintype "passive"))
      (node (ref "J2") (pin "6") (pinfunction "6_6") (pintype "passive"))
      (node (ref "J3") (pin "2") (pinfunction "2_2") (pintype "passive"))
      (node (ref "J4") (pin "2") (pinfunction "2_2") (pintype "passive"))
      (node (ref "J5") (pin "6") (pinfunction "6_6") (pintype "passive"))
      (node (ref "J6") (pin "6") (pinfunction "6_6") (pintype "passive"))
      (node (ref "J7") (pin "10") (pinfunction "SHLD5_10") (pintype "passive"))
      (node (ref "J7") (pin "11") (pinfunction "SHLD6_11") (pintype "passive"))
      (node (ref "J7") (pin "4") (pinfunction "ID_4") (pintype "passive"))
      (node (ref "J7") (pin "5") (pinfunction "GND_5") (pintype "passive"))
      (node (ref "J7") (pin "6") (pinfunction "SHLD1_6") (pintype "passive"))
      (node (ref "J7") (pin "7") (pinfunction "SHLD2_7") (pintype "passive"))
      (node (ref "J7") (pin "8") (pinfunction "SHLD3_8") (pintype "passive"))
      (node (ref "J7") (pin "9") (pinfunction "SHLD4_9") (pintype "passive"))
      (node (ref "J8") (pin "5") (pinfunction "5_5") (pintype "passive"))
      (node (ref "J8") (pin "6") (pinfunction "6_6") (pintype "passive"))
      (node (ref "J8") (pin "7") (pinfunction "7_7") (pintype "passive"))
      (node (ref "J9") (pin "5") (pinfunction "5_5") (pintype "passive"))
      (node (ref "J9") (pin "6") (pinfunction "6_6") (pintype "passive"))
      (node (ref "J9") (pin "7") (pinfunction "7_7") (pintype "passive"))
      (node (ref "Q1") (pin "2") (pinfunction "S_2") (pintype "passive"))
      (node (ref "Q2") (pin "2") (pinfunction "S_2") (pintype "passive"))
      (node (ref "R15") (pin "1") (pinfunction "1_1") (pintype "passive"))
      (node (ref "R21") (pin "1") (pinfunction "1_1") (pintype "passive"))
      (node (ref "R25") (pin "1") (pinfunction "1_1") (pintype "passive"))
      (node (ref "R29") (pin "1") (pinfunction "1_1") (pintype "passive"))
      (node (ref "R5") (pin "1") (pinfunction "1_1") (pintype "passive"))
      (node (ref "R6") (pin "1") (pinfunction "1_1") (pintype "passive"))
      (node (ref "S1") (pin "1") (pinfunction "1_1") (pintype "passive"))
      (node (ref "S1") (pin "2") (pinfunction "2_2") (pintype "passive"))
      (node (ref "U1") (pin "13") (pinfunction "PGND_13") (pintype "passive"))
      (node (ref "U1") (pin "8") (pinfunction "AGND_8") (pintype "passive"))
      (node (ref "U2") (pin "2") (pinfunction "GND_2") (pintype "passive"))
      (node (ref "U3") (pin "3") (pinfunction "GND_3") (pintype "passive"))
      (node (ref "U4") (pin "12") (pinfunction "VSSA/VREF-_12") (pintype "passive"))
      (node (ref "U4") (pin "18") (pinfunction "VSS_18") (pintype "passive"))
      (node (ref "U4") (pin "31") (pinfunction "VSS_31") (pintype "passive"))
      (node (ref "U4") (pin "47") (pinfunction "VSS_47") (pintype "passive"))
      (node (ref "U4") (pin "63") (pinfunction "VSS_63") (pintype "passive"))
      (node (ref "U5") (pin "16") (pinfunction "GND_16") (pintype "passive"))
      (node (ref "U5") (pin "6") (pinfunction "GND_6") (pintype "passive"))
      (node (ref "X1") (pin "2") (pinfunction "GND_2") (pintype "passive"))
      (node (ref "X1") (pin "4") (pinfunction "GND_4") (pintype "passive"))
    )
    (net (code "84") (name "Net-(C11-Pad2)") (class "Default")
      (node (ref "C11") (pin "2") (pinfunction "2_2") (pintype "passive"))
      (node (ref "R4") (pin "1") (pinfunction "1_1") (pintype "passive"))
    )
    (net (code "85") (name "Net-(D1-A)") (class "Default")
      (node (ref "D1") (pin "1") (pinfunction "A_1") (pintype "passive"))
      (node (ref "R2") (pin "1") (pinfunction "1_1") (pintype "passive"))
    )
    (net (code "86") (name "Net-(D4-A)") (class "Default")
      (node (ref "D4") (pin "1") (pinfunction "A_1") (pintype "passive"))
      (node (ref "R7") (pin "1") (pinfunction "1_1") (pintype "passive"))
    )
    (net (code "87") (name "Net-(D5-A)") (class "Default")
      (node (ref "D5") (pin "1") (pinfunction "A_1") (pintype "passive"))
      (node (ref "R8") (pin "1") (pinfunction "1_1") (pintype "passive"))
    )
    (net (code "88") (name "Net-(D6-A)") (class "Default")
      (node (ref "D6") (pin "1") (pinfunction "A_1") (pintype "passive"))
      (node (ref "R17") (pin "1") (pinfunction "1_1") (pintype "passive"))
    )
    (net (code "89") (name "Net-(Q1-D)") (class "Default")
      (node (ref "J13") (pin "2") (pinfunction "2_2") (pintype "passive"))
      (node (ref "Q1") (pin "3") (pinfunction "D_3") (pintype "passive"))
    )
    (net (code "90") (name "Net-(Q2-D)") (class "Default")
      (node (ref "J14") (pin "2") (pinfunction "2_2") (pintype "passive"))
      (node (ref "Q2") (pin "3") (pinfunction "D_3") (pintype "passive"))
    )
    (net (code "91") (name "Net-(Q3-B)") (class "Default")
      (node (ref "Q3") (pin "2") (pinfunction "B_2") (pintype "passive"))
      (node (ref "R42") (pin "1") (pinfunction "1_1") (pintype "passive"))
    )
    (net (code "92") (name "Net-(Q4-B)") (class "Default")
      (node (ref "Q4") (pin "2") (pinfunction "B_2") (pintype "passive"))
      (node (ref "R47") (pin "1") (pinfunction "1_1") (pintype "passive"))
    )
    (net (code "93") (name "Net-(U4-PH0-OSC_IN)") (class "Default")
      (node (ref "C37") (pin "2") (pinfunction "2_2") (pintype "passive"))
      (node (ref "U4") (pin "5") (pinfunction "PH0-OSC_IN_5") (pintype "passive"))
      (node (ref "X1") (pin "3") (pinfunction "3_3") (pintype "passive"))
    )
    (net (code "94") (name "Net-(U4-PH1-OSC_OUT)") (class "Default")
      (node (ref "C38") (pin "2") (pinfunction "2_2") (pintype "passive"))
      (node (ref "U4") (pin "6") (pinfunction "PH1-OSC_OUT_6") (pintype "passive"))
      (node (ref "X1") (pin "1") (pinfunction "1_1") (pintype "passive"))
    )
    (net (code "95") (name "VBUS") (class "Default")
      (node (ref "C1") (pin "1") (pinfunction "1_1") (pintype "passive"))
      (node (ref "C16") (pin "2") (pinfunction "2_2") (pintype "passive"))
      (node (ref "C17") (pin "2") (pinfunction "2_2") (pintype "passive"))
      (node (ref "C2") (pin "2") (pinfunction "2_2") (pintype "passive"))
      (node (ref "C3") (pin "2") (pinfunction "2_2") (pintype "passive"))
      (node (ref "C4") (pin "2") (pinfunction "2_2") (pintype "passive"))
      (node (ref "C5") (pin "2") (pinfunction "2_2") (pintype "passive"))
      (node (ref "J13") (pin "1") (pinfunction "1_1") (pintype "passive"))
      (node (ref "J14") (pin "1") (pinfunction "1_1") (pintype "passive"))
      (node (ref "J3") (pin "1") (pinfunction "1_1") (pintype "passive"))
      (node (ref "R1") (pin "2") (pinfunction "2_2") (pintype "passive"))
      (node (ref "U1") (pin "10") (pinfunction "VIN_10") (pintype "passive"))
      (node (ref "U1") (pin "11") (pinfunction "VIN_11") (pintype "passive"))
      (node (ref "U1") (pin "12") (pinfunction "VIN_12") (pintype "passive"))
      (node (ref "U3") (pin "2") (pinfunction "IN_2") (pintype "passive"))
    )
    (net (code "96") (name "unconnected-(MH1-Pad1)") (class "Default")
      (node (ref "MH1") (pin "1") (pinfunction "1_1") (pintype "passive+no_connect"))
    )
    (net (code "97") (name "unconnected-(MH2-Pad1)") (class "Default")
      (node (ref "MH2") (pin "1") (pinfunction "1_1") (pintype "passive+no_connect"))
    )
    (net (code "98") (name "unconnected-(MH3-Pad1)") (class "Default")
      (node (ref "MH3") (pin "1") (pinfunction "1_1") (pintype "passive+no_connect"))
    )
    (net (code "99") (name "unconnected-(MH4-Pad1)") (class "Default")
      (node (ref "MH4") (pin "1") (pinfunction "1_1") (pintype "passive+no_connect"))
    )
    (net (code "100") (name "unconnected-(U1-PG-Pad5)") (class "Default")
      (node (ref "U1") (pin "5") (pinfunction "PG_5") (pintype "passive+no_connect"))
    )
    (net (code "101") (name "unconnected-(U2-NC-Pad4)") (class "Default")
      (node (ref "U2") (pin "4") (pinfunction "NC_4") (pintype "passive+no_connect"))
    )
    (net (code "102") (name "unconnected-(U4-PA0-Pad14)") (class "Default")
      (node (ref "U4") (pin "14") (pinfunction "PA0_14") (pintype "passive"))
    )
    (net (code "103") (name "unconnected-(U4-PA1-Pad15)") (class "Default")
      (node (ref "U4") (pin "15") (pinfunction "PA1_15") (pintype "passive"))
    )
    (net (code "104") (name "unconnected-(U4-PA4-Pad20)") (class "Default")
      (node (ref "U4") (pin "20") (pinfunction "PA4_20") (pintype "passive"))
    )
    (net (code "105") (name "unconnected-(U4-PA6-Pad22)") (class "Default")
      (node (ref "U4") (pin "22") (pinfunction "PA6_22") (pintype "passive"))
    )
    (net (code "106") (name "unconnected-(U4-PA11-Pad44)") (class "Default")
      (node (ref "U4") (pin "44") (pinfunction "PA11_44") (pintype "passive"))
    )
    (net (code "107") (name "unconnected-(U4-PA12-Pad45)") (class "Default")
      (node (ref "U4") (pin "45") (pinfunction "PA12_45") (pintype "passive"))
    )
    (net (code "108") (name "unconnected-(U4-PB2-Pad28)") (class "Default")
      (node (ref "U4") (pin "28") (pinfunction "PB2_28") (pintype "passive"))
    )
    (net (code "109") (name "unconnected-(U4-PB7-Pad59)") (class "Default")
      (node (ref "U4") (pin "59") (pinfunction "PB7_59") (pintype "passive"))
    )
    (net (code "110") (name "unconnected-(U4-PB10-Pad29)") (class "Default")
      (node (ref "U4") (pin "29") (pinfunction "PB10_29") (pintype "passive"))
    )
    (net (code "111") (name "unconnected-(U4-PB11-Pad30)") (class "Default")
      (node (ref "U4") (pin "30") (pinfunction "PB11_30") (pintype "passive"))
    )
    (net (code "112") (name "unconnected-(U4-PB12-Pad33)") (class "Default")
      (node (ref "U4") (pin "33") (pinfunction "PB12_33") (pintype "passive"))
    )
    (net (code "113") (name "unconnected-(U4-PC1-Pad9)") (class "Default")
      (node (ref "U4") (pin "9") (pinfunction "PC1_9") (pintype "passive"))
    )
    (net (code "114") (name "unconnected-(U4-PC2-Pad10)") (class "Default")
      (node (ref "U4") (pin "10") (pinfunction "PC2_10") (pintype "passive"))
    )
    (net (code "115") (name "unconnected-(U4-PC3-Pad11)") (class "Default")
      (node (ref "U4") (pin "11") (pinfunction "PC3_11") (pintype "passive"))
    )
    (net (code "116") (name "unconnected-(U4-PC7-Pad38)") (class "Default")
      (node (ref "U4") (pin "38") (pinfunction "PC7_38") (pintype "passive"))
    )
    (net (code "117") (name "unconnected-(U4-PC13-Pad2)") (class "Default")
      (node (ref "U4") (pin "2") (pinfunction "PC13_2") (pintype "passive"))
    )
    (net (code "118") (name "unconnected-(U4-PC14-OSC32_IN-Pad3)") (class "Default")
      (node (ref "U4") (pin "3") (pinfunction "PC14-OSC32_IN_3") (pintype "passive+no_connect"))
    )
    (net (code "119") (name "unconnected-(U4-PC15-OSC32_OUT-Pad4)") (class "Default")
      (node (ref "U4") (pin "4") (pinfunction "PC15-OSC32_OUT_4") (pintype "passive+no_connect"))
    )
    (net (code "120") (name "unconnected-(U5-CBUS0-Pad18)") (class "Default")
      (node (ref "U5") (pin "18") (pinfunction "CBUS0_18") (pintype "passive+no_connect"))
    )
    (net (code "121") (name "unconnected-(U5-CBUS1-Pad17)") (class "Default")
      (node (ref "U5") (pin "17") (pinfunction "CBUS1_17") (pintype "passive+no_connect"))
    )
    (net (code "122") (name "unconnected-(U5-CBUS2-Pad10)") (class "Default")
      (node (ref "U5") (pin "10") (pinfunction "CBUS2_10") (pintype "passive+no_connect"))
    )
    (net (code "123") (name "unconnected-(U5-CBUS3-Pad19)") (class "Default")
      (node (ref "U5") (pin "19") (pinfunction "CBUS3_19") (pintype "passive+no_connect"))
    )
    (net (code "124") (name "unconnected-(U5-CTS#-Pad9)") (class "Default")
      (node (ref "U5") (pin "9") (pinfunction "CTS#_9") (pintype "passive+no_connect"))
    )
    (net (code "125") (name "unconnected-(U5-DCD#-Pad8)") (class "Default")
      (node (ref "U5") (pin "8") (pinfunction "DCD#_8") (pintype "passive+no_connect"))
    )
    (net (code "126") (name "unconnected-(U5-DSR#-Pad7)") (class "Default")
      (node (ref "U5") (pin "7") (pinfunction "DSR#_7") (pintype "passive+no_connect"))
    )
    (net (code "127") (name "unconnected-(U5-RI#-Pad5)") (class "Default")
      (node (ref "U5") (pin "5") (pinfunction "RI#_5") (pintype "passive+no_connect"))
    )
  )
)
